# backplane.net
KiCad netlist of a schematic drawn in EAGLE
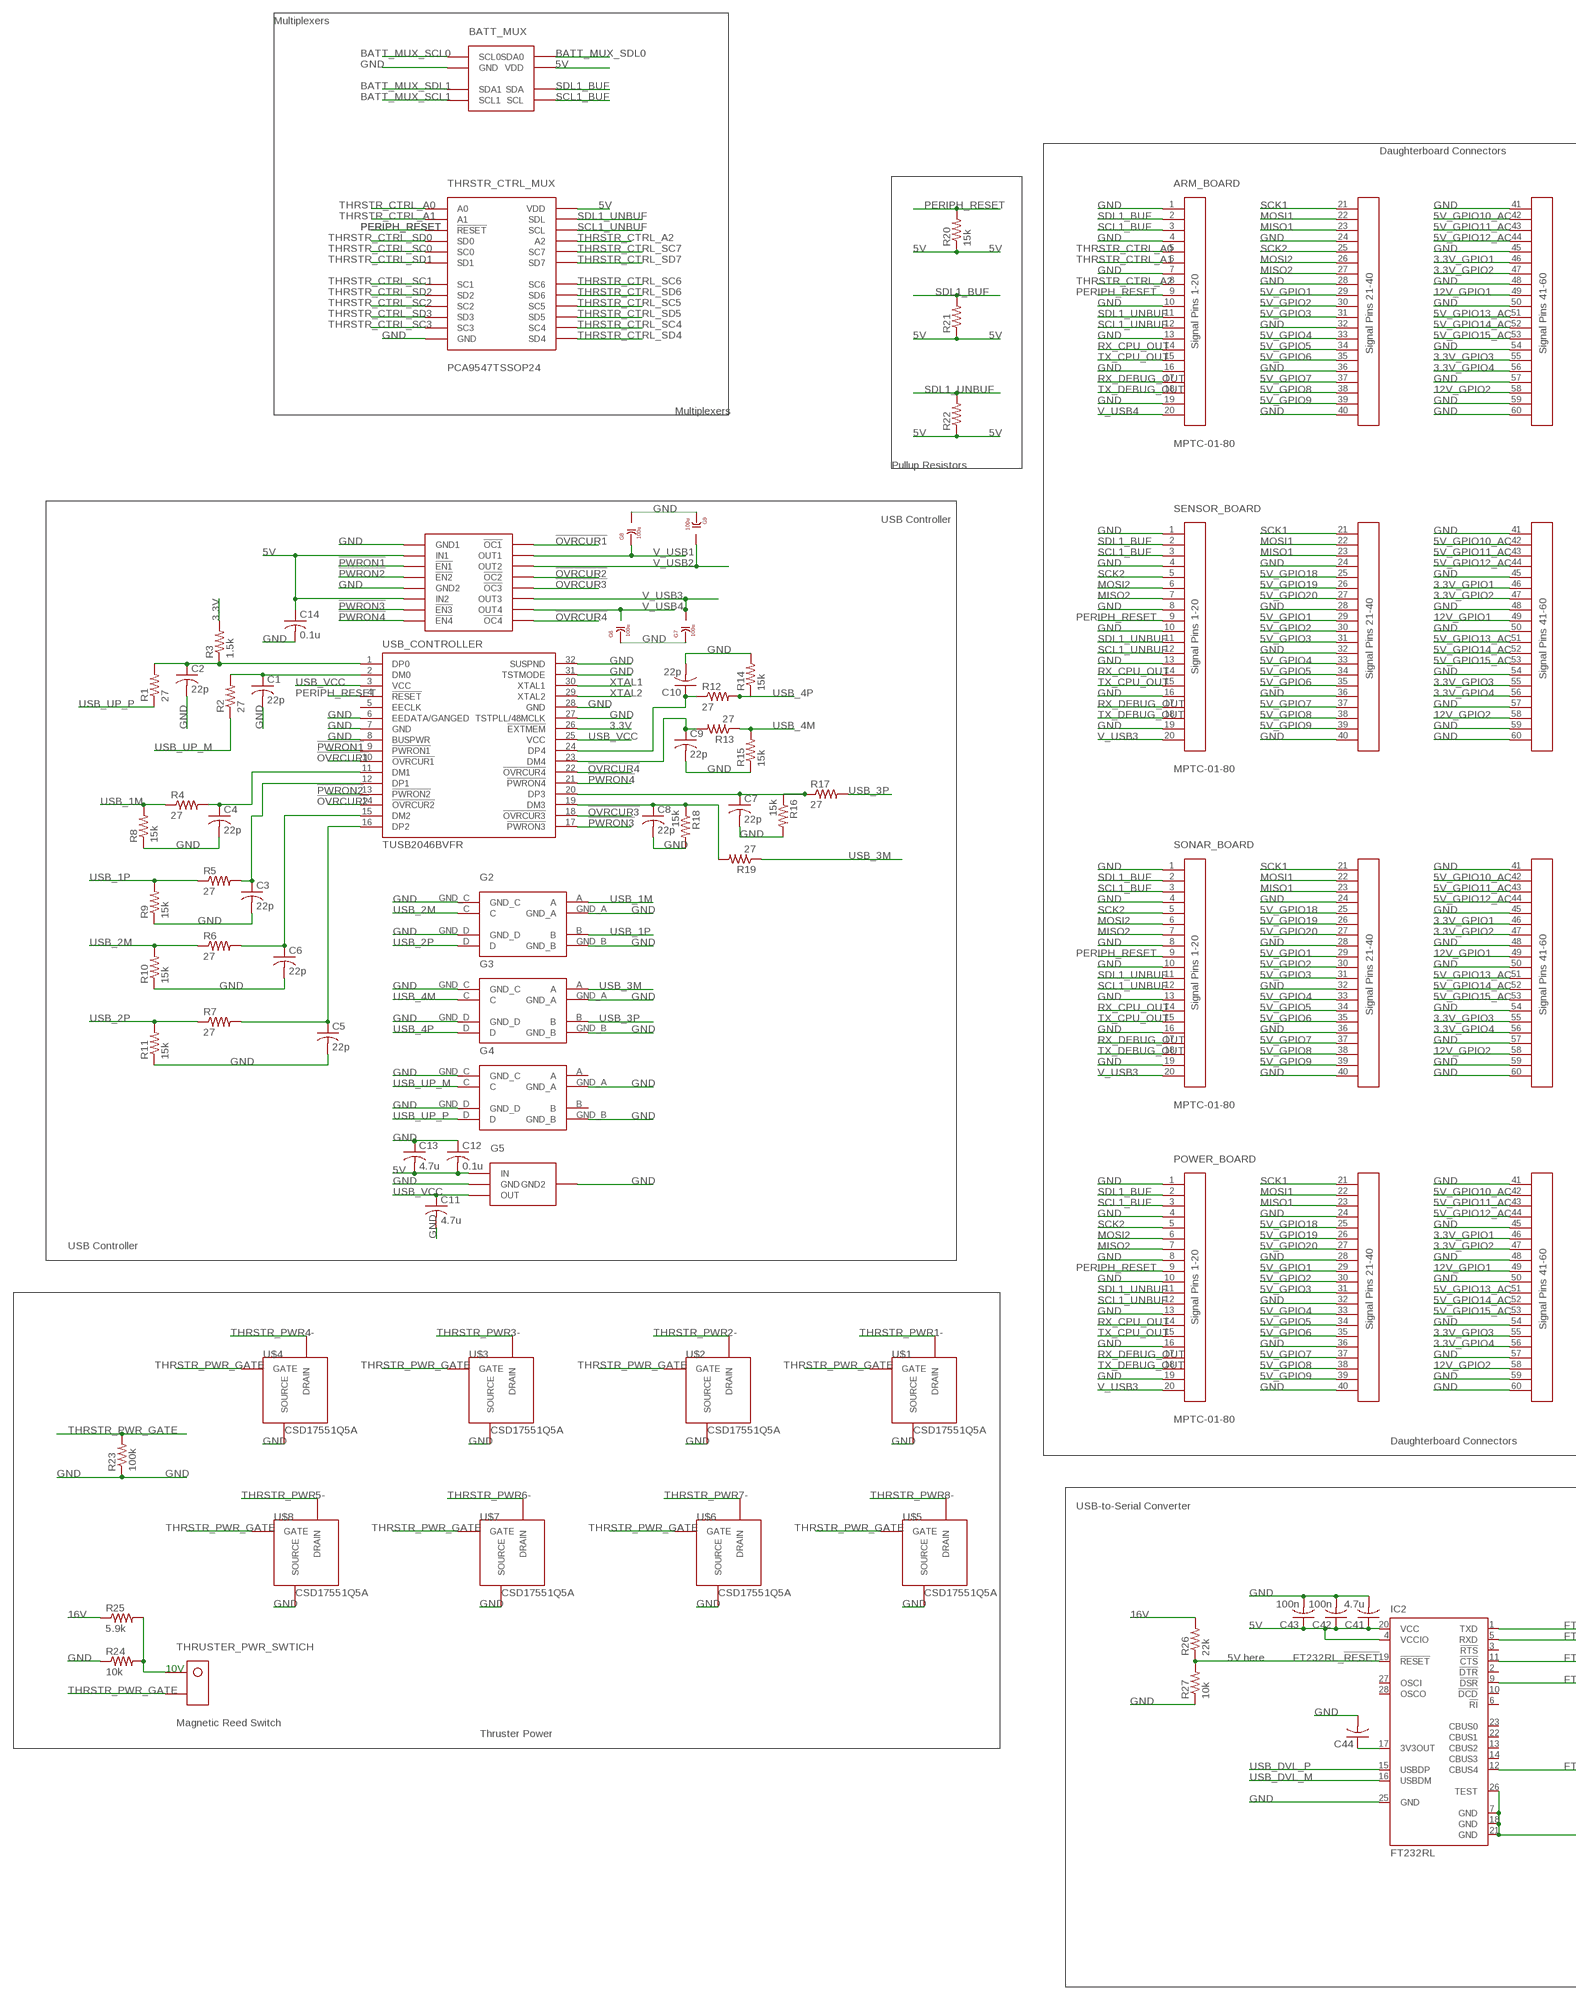
[diagram p0: schematic, sheet 1, part 1 of 2]
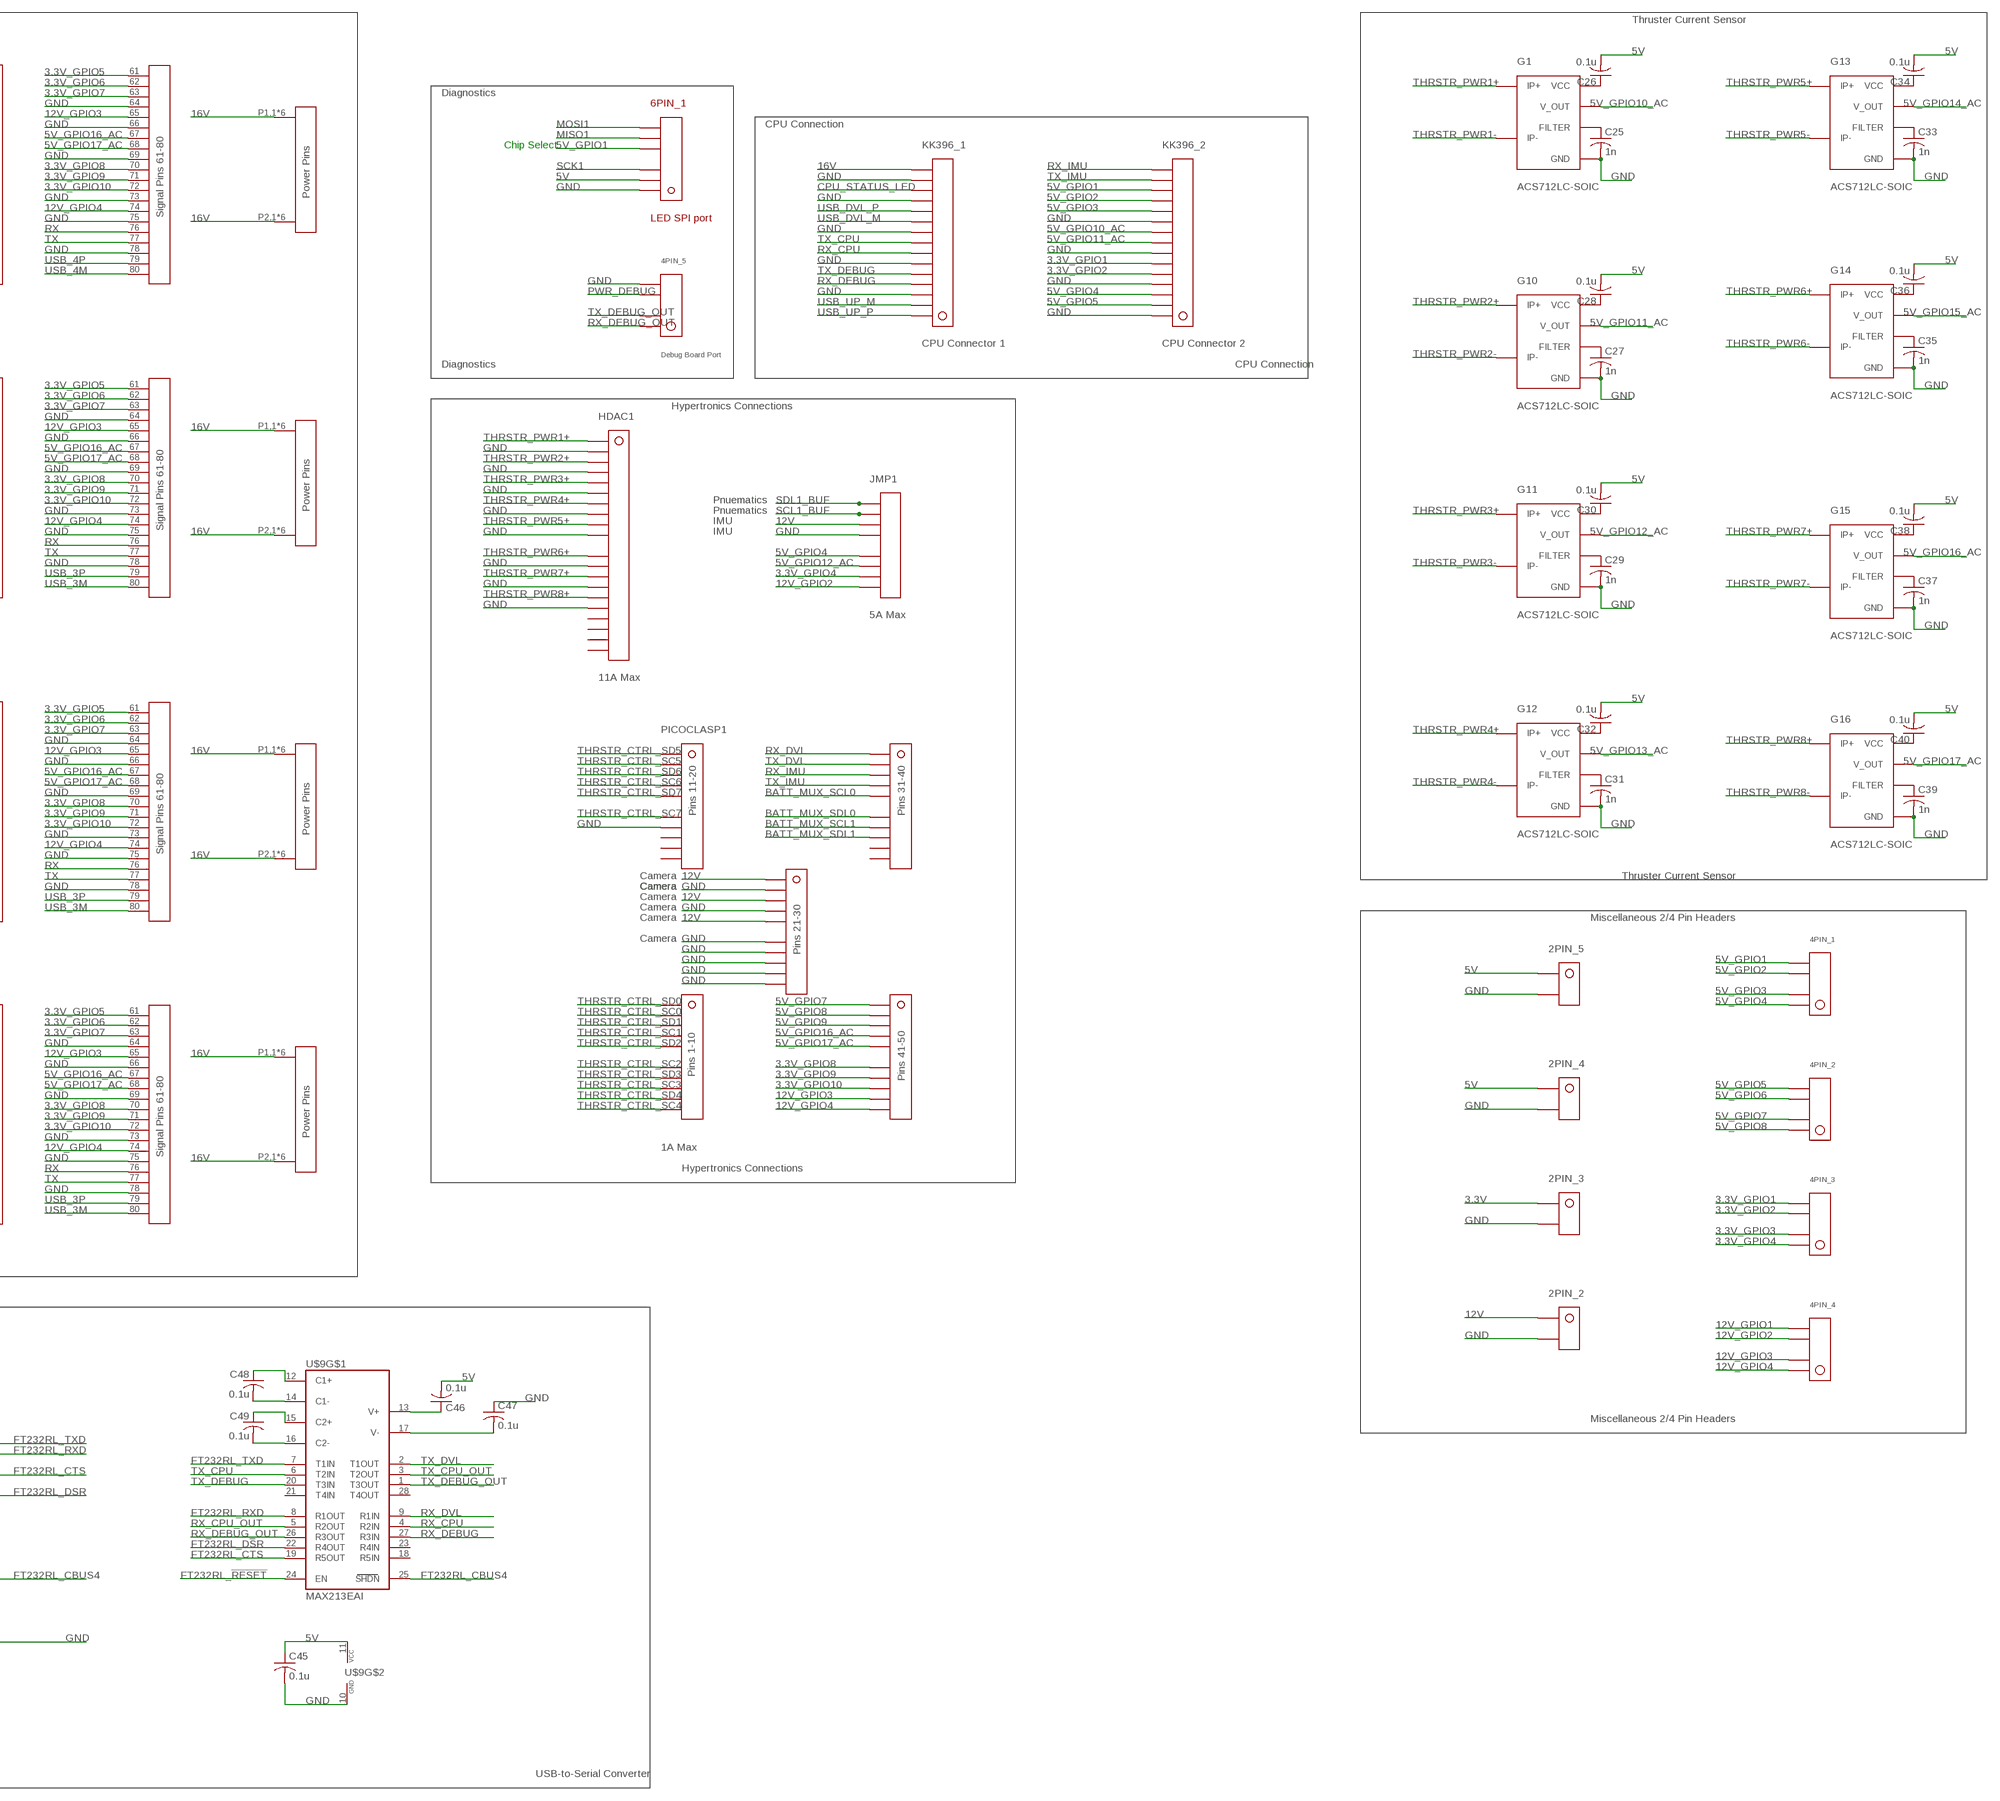
[diagram p1: schematic, sheet 1, part 2 of 2]

(export (version "E")
  (design (tool "Eeschema 10.0.6"))
  (components
    (comp (ref "2PIN_2")
      (value "KK254_VERT_2PIN22-29-2021")
      (footprint "eagle-import:KK254_VERT_2PIN")
      (libsource (lib "eagle-import") (part "KK254_VERT_2PIN22-29-2021"))
    )
    (comp (ref "2PIN_3")
      (value "KK254_VERT_2PIN22-29-2021")
      (footprint "eagle-import:KK254_VERT_2PIN")
      (libsource (lib "eagle-import") (part "KK254_VERT_2PIN22-29-2021"))
    )
    (comp (ref "2PIN_4")
      (value "KK254_VERT_2PIN22-29-2021")
      (footprint "eagle-import:KK254_VERT_2PIN")
      (libsource (lib "eagle-import") (part "KK254_VERT_2PIN22-29-2021"))
    )
    (comp (ref "2PIN_5")
      (value "KK254_VERT_2PIN22-29-2021")
      (footprint "eagle-import:KK254_VERT_2PIN")
      (libsource (lib "eagle-import") (part "KK254_VERT_2PIN22-29-2021"))
    )
    (comp (ref "4PIN_1")
      (value "KK254_VERT_4PIN22-29-2041")
      (footprint "eagle-import:KK254_VERT_4PIN")
      (libsource (lib "eagle-import") (part "KK254_VERT_4PIN22-29-2041"))
    )
    (comp (ref "4PIN_2")
      (value "KK254_VERT_4PIN22-29-2041")
      (footprint "eagle-import:KK254_VERT_4PIN")
      (libsource (lib "eagle-import") (part "KK254_VERT_4PIN22-29-2041"))
    )
    (comp (ref "4PIN_3")
      (value "KK254_VERT_4PIN22-29-2041")
      (footprint "eagle-import:KK254_VERT_4PIN")
      (libsource (lib "eagle-import") (part "KK254_VERT_4PIN22-29-2041"))
    )
    (comp (ref "4PIN_4")
      (value "KK254_VERT_4PIN22-29-2041")
      (footprint "eagle-import:KK254_VERT_4PIN")
      (libsource (lib "eagle-import") (part "KK254_VERT_4PIN22-29-2041"))
    )
    (comp (ref "4PIN_5")
      (value "Debug Board Port")
      (footprint "eagle-import:KK254_VERT_4PIN")
      (libsource (lib "eagle-import") (part "KK254_VERT_4PIN22-29-2041"))
    )
    (comp (ref "6PIN_1")
      (value "LED SPI port")
      (footprint "eagle-import:KK254_6PIN")
      (libsource (lib "eagle-import") (part "KK254_6PIN"))
    )
    (comp (ref "ARM_BOARD")
      (value "MPTC-01-80")
      (footprint "eagle-import:MPTC-01-80")
      (libsource (lib "eagle-import") (part "MPTC-01-80"))
    )
    (comp (ref "BATT_MUX")
      (value "PCA9540BTSSOP8")
      (footprint "eagle-import:PCA9540B")
      (libsource (lib "eagle-import") (part "PCA9540BTSSOP8"))
    )
    (comp (ref "C1")
      (value "22p")
      (footprint "eagle-import:C0603")
      (libsource (lib "eagle-import") (part "C-USC0603"))
    )
    (comp (ref "C2")
      (value "22p")
      (footprint "eagle-import:C0603")
      (libsource (lib "eagle-import") (part "C-USC0603"))
    )
    (comp (ref "C3")
      (value "22p")
      (footprint "eagle-import:C0603")
      (libsource (lib "eagle-import") (part "C-USC0603"))
    )
    (comp (ref "C4")
      (value "22p")
      (footprint "eagle-import:C0603")
      (libsource (lib "eagle-import") (part "C-USC0603"))
    )
    (comp (ref "C5")
      (value "22p")
      (footprint "eagle-import:C0603")
      (libsource (lib "eagle-import") (part "C-USC0603"))
    )
    (comp (ref "C6")
      (value "22p")
      (footprint "eagle-import:C0603")
      (libsource (lib "eagle-import") (part "C-USC0603"))
    )
    (comp (ref "C7")
      (value "22p")
      (footprint "eagle-import:C0603")
      (libsource (lib "eagle-import") (part "C-USC0603"))
    )
    (comp (ref "C8")
      (value "22p")
      (footprint "eagle-import:C0603")
      (libsource (lib "eagle-import") (part "C-USC0603"))
    )
    (comp (ref "C9")
      (value "22p")
      (footprint "eagle-import:C0603")
      (libsource (lib "eagle-import") (part "C-USC0603"))
    )
    (comp (ref "C10")
      (value "22p")
      (footprint "eagle-import:C0603")
      (libsource (lib "eagle-import") (part "C-USC0603"))
    )
    (comp (ref "C11")
      (value "4.7u")
      (footprint "eagle-import:C0603")
      (libsource (lib "eagle-import") (part "C-USC0603"))
    )
    (comp (ref "C12")
      (value "0.1u")
      (footprint "eagle-import:C0603")
      (libsource (lib "eagle-import") (part "C-USC0603"))
    )
    (comp (ref "C13")
      (value "4.7u")
      (footprint "eagle-import:C0603")
      (libsource (lib "eagle-import") (part "C-USC0603"))
    )
    (comp (ref "C14")
      (value "0.1u")
      (footprint "eagle-import:C0603")
      (libsource (lib "eagle-import") (part "C-USC0603"))
    )
    (comp (ref "C25")
      (value "1n")
      (footprint "eagle-import:C0603")
      (libsource (lib "eagle-import") (part "C-USC0603"))
    )
    (comp (ref "C26")
      (value "0.1u")
      (footprint "eagle-import:C0603")
      (libsource (lib "eagle-import") (part "C-USC0603"))
    )
    (comp (ref "C27")
      (value "1n")
      (footprint "eagle-import:C0603")
      (libsource (lib "eagle-import") (part "C-USC0603"))
    )
    (comp (ref "C28")
      (value "0.1u")
      (footprint "eagle-import:C0603")
      (libsource (lib "eagle-import") (part "C-USC0603"))
    )
    (comp (ref "C29")
      (value "1n")
      (footprint "eagle-import:C0603")
      (libsource (lib "eagle-import") (part "C-USC0603"))
    )
    (comp (ref "C30")
      (value "0.1u")
      (footprint "eagle-import:C0603")
      (libsource (lib "eagle-import") (part "C-USC0603"))
    )
    (comp (ref "C31")
      (value "1n")
      (footprint "eagle-import:C0603")
      (libsource (lib "eagle-import") (part "C-USC0603"))
    )
    (comp (ref "C32")
      (value "0.1u")
      (footprint "eagle-import:C0603")
      (libsource (lib "eagle-import") (part "C-USC0603"))
    )
    (comp (ref "C33")
      (value "1n")
      (footprint "eagle-import:C0603")
      (libsource (lib "eagle-import") (part "C-USC0603"))
    )
    (comp (ref "C34")
      (value "0.1u")
      (footprint "eagle-import:C0603")
      (libsource (lib "eagle-import") (part "C-USC0603"))
    )
    (comp (ref "C35")
      (value "1n")
      (footprint "eagle-import:C0603")
      (libsource (lib "eagle-import") (part "C-USC0603"))
    )
    (comp (ref "C36")
      (value "0.1u")
      (footprint "eagle-import:C0603")
      (libsource (lib "eagle-import") (part "C-USC0603"))
    )
    (comp (ref "C37")
      (value "1n")
      (footprint "eagle-import:C0603")
      (libsource (lib "eagle-import") (part "C-USC0603"))
    )
    (comp (ref "C38")
      (value "0.1u")
      (footprint "eagle-import:C0603")
      (libsource (lib "eagle-import") (part "C-USC0603"))
    )
    (comp (ref "C39")
      (value "1n")
      (footprint "eagle-import:C0603")
      (libsource (lib "eagle-import") (part "C-USC0603"))
    )
    (comp (ref "C40")
      (value "0.1u")
      (footprint "eagle-import:C0603")
      (libsource (lib "eagle-import") (part "C-USC0603"))
    )
    (comp (ref "C41")
      (value "4.7u")
      (footprint "eagle-import:C0603")
      (libsource (lib "eagle-import") (part "C-USC0603"))
    )
    (comp (ref "C42")
      (value "100n")
      (footprint "eagle-import:C0603")
      (libsource (lib "eagle-import") (part "C-USC0603"))
    )
    (comp (ref "C43")
      (value "100n")
      (footprint "eagle-import:C0603")
      (libsource (lib "eagle-import") (part "C-USC0603"))
    )
    (comp (ref "C44")
      (value "C-USC0603")
      (footprint "eagle-import:C0603")
      (libsource (lib "eagle-import") (part "C-USC0603"))
    )
    (comp (ref "C45")
      (value "0.1u")
      (footprint "eagle-import:C0603")
      (libsource (lib "eagle-import") (part "C-USC0603"))
    )
    (comp (ref "C46")
      (value "0.1u")
      (footprint "eagle-import:C0603")
      (libsource (lib "eagle-import") (part "C-USC0603"))
    )
    (comp (ref "C47")
      (value "0.1u")
      (footprint "eagle-import:C0603")
      (libsource (lib "eagle-import") (part "C-USC0603"))
    )
    (comp (ref "C48")
      (value "0.1u")
      (footprint "eagle-import:C0603")
      (libsource (lib "eagle-import") (part "C-USC0603"))
    )
    (comp (ref "C49")
      (value "0.1u")
      (footprint "eagle-import:C0603")
      (libsource (lib "eagle-import") (part "C-USC0603"))
    )
    (comp (ref "G1")
      (value "ACS712LC-SOIC")
      (footprint "eagle-import:ACS712-SOIC")
      (libsource (lib "eagle-import") (part "ACS712LC-SOIC"))
    )
    (comp (ref "G2")
      (value "SN75240PW'TSSOP")
      (footprint "eagle-import:SN75240PW")
      (libsource (lib "eagle-import") (part "SN75240PW'TSSOP"))
    )
    (comp (ref "G3")
      (value "SN75240PW'TSSOP")
      (footprint "eagle-import:SN75240PW")
      (libsource (lib "eagle-import") (part "SN75240PW'TSSOP"))
    )
    (comp (ref "G4")
      (value "SN75240PW'TSSOP")
      (footprint "eagle-import:SN75240PW")
      (libsource (lib "eagle-import") (part "SN75240PW'TSSOP"))
    )
    (comp (ref "G5")
      (value "LM3940IMP-3.3/NOPB")
      (footprint "eagle-import:SOT223-DCY")
      (libsource (lib "eagle-import") (part "LM3940IMP-3.3/NOPB"))
    )
    (comp (ref "G6")
      (value "100u")
      (footprint "eagle-import:F930J107MBA")
      (libsource (lib "eagle-import") (part "F930J107MBA"))
    )
    (comp (ref "G7")
      (value "100u")
      (footprint "eagle-import:F930J107MBA")
      (libsource (lib "eagle-import") (part "F930J107MBA"))
    )
    (comp (ref "G8")
      (value "100u")
      (footprint "eagle-import:F930J107MBA")
      (libsource (lib "eagle-import") (part "F930J107MBA"))
    )
    (comp (ref "G9")
      (value "100u")
      (footprint "eagle-import:F930J107MBA")
      (libsource (lib "eagle-import") (part "F930J107MBA"))
    )
    (comp (ref "G10")
      (value "ACS712LC-SOIC")
      (footprint "eagle-import:ACS712-SOIC")
      (libsource (lib "eagle-import") (part "ACS712LC-SOIC"))
    )
    (comp (ref "G11")
      (value "ACS712LC-SOIC")
      (footprint "eagle-import:ACS712-SOIC")
      (libsource (lib "eagle-import") (part "ACS712LC-SOIC"))
    )
    (comp (ref "G12")
      (value "ACS712LC-SOIC")
      (footprint "eagle-import:ACS712-SOIC")
      (libsource (lib "eagle-import") (part "ACS712LC-SOIC"))
    )
    (comp (ref "G13")
      (value "ACS712LC-SOIC")
      (footprint "eagle-import:ACS712-SOIC")
      (libsource (lib "eagle-import") (part "ACS712LC-SOIC"))
    )
    (comp (ref "G14")
      (value "ACS712LC-SOIC")
      (footprint "eagle-import:ACS712-SOIC")
      (libsource (lib "eagle-import") (part "ACS712LC-SOIC"))
    )
    (comp (ref "G15")
      (value "ACS712LC-SOIC")
      (footprint "eagle-import:ACS712-SOIC")
      (libsource (lib "eagle-import") (part "ACS712LC-SOIC"))
    )
    (comp (ref "G16")
      (value "ACS712LC-SOIC")
      (footprint "eagle-import:ACS712-SOIC")
      (libsource (lib "eagle-import") (part "ACS712LC-SOIC"))
    )
    (comp (ref "HDAC1")
      (value "11A Max")
      (footprint "eagle-import:HDAC64_VERT_20PIN")
      (libsource (lib "eagle-import") (part "HDAC64_VERT_20PIN30700-4122"))
    )
    (comp (ref "IC2")
      (value "FT232RL")
      (footprint "eagle-import:SSOP28")
      (libsource (lib "eagle-import") (part "FT232RL"))
    )
    (comp (ref "JMP1")
      (value "5A Max")
      (footprint "eagle-import:MICROFIT3_VERT_8PIN")
      (libsource (lib "eagle-import") (part "MICROFIT3_VERT_8PIN43045-0828"))
    )
    (comp (ref "KK396_1")
      (value "CPU Connector 1")
      (footprint "eagle-import:KK396_VERT_15PIN")
      (libsource (lib "eagle-import") (part "KK396_VERT_15PIN"))
    )
    (comp (ref "KK396_2")
      (value "CPU Connector 2")
      (footprint "eagle-import:KK396_VERT_15PIN")
      (libsource (lib "eagle-import") (part "KK396_VERT_15PIN"))
    )
    (comp (ref "PICOCLASP1")
      (value "1A Max")
      (footprint "eagle-import:PICOCLASP_VERT_50PIN")
      (libsource (lib "eagle-import") (part "PICOCLASP_VERT_50PINSMD"))
    )
    (comp (ref "POWER_BOARD")
      (value "MPTC-01-80")
      (footprint "eagle-import:MPTC-01-80")
      (libsource (lib "eagle-import") (part "MPTC-01-80"))
    )
    (comp (ref "R1")
      (value "27")
      (footprint "eagle-import:R0603")
      (libsource (lib "eagle-import") (part "R-US_R0603"))
    )
    (comp (ref "R2")
      (value "27")
      (footprint "eagle-import:R0603")
      (libsource (lib "eagle-import") (part "R-US_R0603"))
    )
    (comp (ref "R3")
      (value "1.5k")
      (footprint "eagle-import:R0603")
      (libsource (lib "eagle-import") (part "R-US_R0603"))
    )
    (comp (ref "R4")
      (value "27")
      (footprint "eagle-import:R0603")
      (libsource (lib "eagle-import") (part "R-US_R0603"))
    )
    (comp (ref "R5")
      (value "27")
      (footprint "eagle-import:R0603")
      (libsource (lib "eagle-import") (part "R-US_R0603"))
    )
    (comp (ref "R6")
      (value "27")
      (footprint "eagle-import:R0603")
      (libsource (lib "eagle-import") (part "R-US_R0603"))
    )
    (comp (ref "R7")
      (value "27")
      (footprint "eagle-import:R0603")
      (libsource (lib "eagle-import") (part "R-US_R0603"))
    )
    (comp (ref "R8")
      (value "15k")
      (footprint "eagle-import:R0603")
      (libsource (lib "eagle-import") (part "R-US_R0603"))
    )
    (comp (ref "R9")
      (value "15k")
      (footprint "eagle-import:R0603")
      (libsource (lib "eagle-import") (part "R-US_R0603"))
    )
    (comp (ref "R10")
      (value "15k")
      (footprint "eagle-import:R0603")
      (libsource (lib "eagle-import") (part "R-US_R0603"))
    )
    (comp (ref "R11")
      (value "15k")
      (footprint "eagle-import:R0603")
      (libsource (lib "eagle-import") (part "R-US_R0603"))
    )
    (comp (ref "R12")
      (value "27")
      (footprint "eagle-import:R0603")
      (libsource (lib "eagle-import") (part "R-US_R0603"))
    )
    (comp (ref "R13")
      (value "27")
      (footprint "eagle-import:R0603")
      (libsource (lib "eagle-import") (part "R-US_R0603"))
    )
    (comp (ref "R14")
      (value "15k")
      (footprint "eagle-import:R0603")
      (libsource (lib "eagle-import") (part "R-US_R0603"))
    )
    (comp (ref "R15")
      (value "15k")
      (footprint "eagle-import:R0603")
      (libsource (lib "eagle-import") (part "R-US_R0603"))
    )
    (comp (ref "R16")
      (value "15k")
      (footprint "eagle-import:R0603")
      (libsource (lib "eagle-import") (part "R-US_R0603"))
    )
    (comp (ref "R17")
      (value "27")
      (footprint "eagle-import:R0603")
      (libsource (lib "eagle-import") (part "R-US_R0603"))
    )
    (comp (ref "R18")
      (value "15k")
      (footprint "eagle-import:R0603")
      (libsource (lib "eagle-import") (part "R-US_R0603"))
    )
    (comp (ref "R19")
      (value "27")
      (footprint "eagle-import:R0603")
      (libsource (lib "eagle-import") (part "R-US_R0603"))
    )
    (comp (ref "R20")
      (value "15k")
      (footprint "eagle-import:R0603")
      (libsource (lib "eagle-import") (part "R-US_R0603"))
    )
    (comp (ref "R21")
      (value "R-US_R0603")
      (footprint "eagle-import:R0603")
      (libsource (lib "eagle-import") (part "R-US_R0603"))
    )
    (comp (ref "R22")
      (value "R-US_R0603")
      (footprint "eagle-import:R0603")
      (libsource (lib "eagle-import") (part "R-US_R0603"))
    )
    (comp (ref "R23")
      (value "100k")
      (footprint "eagle-import:R0603")
      (libsource (lib "eagle-import") (part "R-US_R0603"))
    )
    (comp (ref "R24")
      (value "10k")
      (footprint "eagle-import:R0603")
      (libsource (lib "eagle-import") (part "R-US_R0603"))
    )
    (comp (ref "R25")
      (value "5.9k")
      (footprint "eagle-import:R0603")
      (libsource (lib "eagle-import") (part "R-US_R0603"))
    )
    (comp (ref "R26")
      (value "22k")
      (footprint "eagle-import:R0603")
      (libsource (lib "eagle-import") (part "R-US_R0603"))
    )
    (comp (ref "R27")
      (value "10k")
      (footprint "eagle-import:R0603")
      (libsource (lib "eagle-import") (part "R-US_R0603"))
    )
    (comp (ref "SENSOR_BOARD")
      (value "MPTC-01-80")
      (footprint "eagle-import:MPTC-01-80")
      (libsource (lib "eagle-import") (part "MPTC-01-80"))
    )
    (comp (ref "SONAR_BOARD")
      (value "MPTC-01-80")
      (footprint "eagle-import:MPTC-01-80")
      (libsource (lib "eagle-import") (part "MPTC-01-80"))
    )
    (comp (ref "THRSTR_CTRL_MUX")
      (value "PCA9547TSSOP24")
      (footprint "eagle-import:PCA9547_TSSOP24")
      (libsource (lib "eagle-import") (part "PCA9547TSSOP24"))
    )
    (comp (ref "THRUSTER_PWR_SWTICH")
      (value "Magnetic Reed Switch")
      (footprint "eagle-import:KK254_VERT_2PIN")
      (libsource (lib "eagle-import") (part "KK254_VERT_2PIN22-29-2021"))
    )
    (comp (ref "U$1")
      (value "CSD17551Q5A")
      (footprint "eagle-import:CSD17551Q5A")
      (libsource (lib "eagle-import") (part "CSD17551Q5A"))
    )
    (comp (ref "U$2")
      (value "CSD17551Q5A")
      (footprint "eagle-import:CSD17551Q5A")
      (libsource (lib "eagle-import") (part "CSD17551Q5A"))
    )
    (comp (ref "U$3")
      (value "CSD17551Q5A")
      (footprint "eagle-import:CSD17551Q5A")
      (libsource (lib "eagle-import") (part "CSD17551Q5A"))
    )
    (comp (ref "U$4")
      (value "CSD17551Q5A")
      (footprint "eagle-import:CSD17551Q5A")
      (libsource (lib "eagle-import") (part "CSD17551Q5A"))
    )
    (comp (ref "U$5")
      (value "CSD17551Q5A")
      (footprint "eagle-import:CSD17551Q5A")
      (libsource (lib "eagle-import") (part "CSD17551Q5A"))
    )
    (comp (ref "U$6")
      (value "CSD17551Q5A")
      (footprint "eagle-import:CSD17551Q5A")
      (libsource (lib "eagle-import") (part "CSD17551Q5A"))
    )
    (comp (ref "U$7")
      (value "CSD17551Q5A")
      (footprint "eagle-import:CSD17551Q5A")
      (libsource (lib "eagle-import") (part "CSD17551Q5A"))
    )
    (comp (ref "U$8")
      (value "CSD17551Q5A")
      (footprint "eagle-import:CSD17551Q5A")
      (libsource (lib "eagle-import") (part "CSD17551Q5A"))
    )
    (comp (ref "U$9")
      (value "MAX213EAI")
      (footprint "eagle-import:SSOP28")
      (libsource (lib "eagle-import") (part "MAX213EAI"))
    )
    (comp (ref "USB_CONTROLLER")
      (value "TUSB2046BVFR")
      (footprint "eagle-import:VF_S-PQFP-G32")
      (fields (field (name "MF") "TEXAS INSTRUMENTS"))
      (libsource (lib "eagle-import") (part "TUSB2046BVFR"))
    )
    (comp (ref "USB_CURRENT")
      (value "TPS2044BBD-SOIC")
      (footprint "eagle-import:TPS2044")
      (libsource (lib "eagle-import") (part "TPS2044BBD-SOIC"))
    )
  )
  (nets
    (net (code "1") (name "/3.3V") (class "Default")
      (node (ref "2PIN_3") (pin "P$1") (pinfunction "P$1_P$1") (pintype "bidirectional"))
      (node (ref "R3") (pin "2") (pinfunction "2_2") (pintype "passive"))
      (node (ref "USB_CONTROLLER") (pin "26") (pinfunction "~{EXTMEM}_26") (pintype "input"))
    )
    (net (code "2") (name "/3.3V_GPIO1") (class "Default")
      (node (ref "4PIN_3") (pin "P$4") (pinfunction "P$4_P$4") (pintype "bidirectional"))
      (node (ref "ARM_BOARD") (pin "46") (pinfunction "P$46_46") (pintype "bidirectional"))
      (node (ref "KK396_2") (pin "P$6") (pinfunction "P$6_P$6") (pintype "bidirectional"))
      (node (ref "POWER_BOARD") (pin "46") (pinfunction "P$46_46") (pintype "bidirectional"))
      (node (ref "SENSOR_BOARD") (pin "46") (pinfunction "P$46_46") (pintype "bidirectional"))
      (node (ref "SONAR_BOARD") (pin "46") (pinfunction "P$46_46") (pintype "bidirectional"))
    )
    (net (code "3") (name "/3.3V_GPIO2") (class "Default")
      (node (ref "4PIN_3") (pin "P$3") (pinfunction "P$3_P$3") (pintype "bidirectional"))
      (node (ref "ARM_BOARD") (pin "47") (pinfunction "P$47_47") (pintype "bidirectional"))
      (node (ref "KK396_2") (pin "P$5") (pinfunction "P$5_P$5") (pintype "bidirectional"))
      (node (ref "POWER_BOARD") (pin "47") (pinfunction "P$47_47") (pintype "bidirectional"))
      (node (ref "SENSOR_BOARD") (pin "47") (pinfunction "P$47_47") (pintype "bidirectional"))
      (node (ref "SONAR_BOARD") (pin "47") (pinfunction "P$47_47") (pintype "bidirectional"))
    )
    (net (code "4") (name "/3.3V_GPIO3") (class "Default")
      (node (ref "4PIN_3") (pin "P$2") (pinfunction "P$2_P$2") (pintype "bidirectional"))
      (node (ref "ARM_BOARD") (pin "55") (pinfunction "P$55_55") (pintype "bidirectional"))
      (node (ref "POWER_BOARD") (pin "55") (pinfunction "P$55_55") (pintype "bidirectional"))
      (node (ref "SENSOR_BOARD") (pin "55") (pinfunction "P$55_55") (pintype "bidirectional"))
      (node (ref "SONAR_BOARD") (pin "55") (pinfunction "P$55_55") (pintype "bidirectional"))
    )
    (net (code "5") (name "/3.3V_GPIO4") (class "Default")
      (node (ref "4PIN_3") (pin "P$1") (pinfunction "P$1_P$1") (pintype "bidirectional"))
      (node (ref "ARM_BOARD") (pin "56") (pinfunction "P$56_56") (pintype "bidirectional"))
      (node (ref "JMP1") (pin "P$2") (pinfunction "P$2_P$2") (pintype "bidirectional"))
      (node (ref "POWER_BOARD") (pin "56") (pinfunction "P$56_56") (pintype "bidirectional"))
      (node (ref "SENSOR_BOARD") (pin "56") (pinfunction "P$56_56") (pintype "bidirectional"))
      (node (ref "SONAR_BOARD") (pin "56") (pinfunction "P$56_56") (pintype "bidirectional"))
    )
    (net (code "6") (name "/3.3V_GPIO5") (class "Default")
      (node (ref "ARM_BOARD") (pin "61") (pinfunction "P$61_61") (pintype "bidirectional"))
      (node (ref "POWER_BOARD") (pin "61") (pinfunction "P$61_61") (pintype "bidirectional"))
      (node (ref "SENSOR_BOARD") (pin "61") (pinfunction "P$61_61") (pintype "bidirectional"))
      (node (ref "SONAR_BOARD") (pin "61") (pinfunction "P$61_61") (pintype "bidirectional"))
    )
    (net (code "7") (name "/3.3V_GPIO6") (class "Default")
      (node (ref "ARM_BOARD") (pin "62") (pinfunction "P$62_62") (pintype "bidirectional"))
      (node (ref "POWER_BOARD") (pin "62") (pinfunction "P$62_62") (pintype "bidirectional"))
      (node (ref "SENSOR_BOARD") (pin "62") (pinfunction "P$62_62") (pintype "bidirectional"))
      (node (ref "SONAR_BOARD") (pin "62") (pinfunction "P$62_62") (pintype "bidirectional"))
    )
    (net (code "8") (name "/3.3V_GPIO7") (class "Default")
      (node (ref "ARM_BOARD") (pin "63") (pinfunction "P$63_63") (pintype "bidirectional"))
      (node (ref "POWER_BOARD") (pin "63") (pinfunction "P$63_63") (pintype "bidirectional"))
      (node (ref "SENSOR_BOARD") (pin "63") (pinfunction "P$63_63") (pintype "bidirectional"))
      (node (ref "SONAR_BOARD") (pin "63") (pinfunction "P$63_63") (pintype "bidirectional"))
    )
    (net (code "9") (name "/3.3V_GPIO8") (class "Default")
      (node (ref "ARM_BOARD") (pin "70") (pinfunction "P$70_70") (pintype "bidirectional"))
      (node (ref "PICOCLASP1") (pin "P$46") (pinfunction "P$46_P$46") (pintype "bidirectional"))
      (node (ref "POWER_BOARD") (pin "70") (pinfunction "P$70_70") (pintype "bidirectional"))
      (node (ref "SENSOR_BOARD") (pin "70") (pinfunction "P$70_70") (pintype "bidirectional"))
      (node (ref "SONAR_BOARD") (pin "70") (pinfunction "P$70_70") (pintype "bidirectional"))
    )
    (net (code "10") (name "/3.3V_GPIO9") (class "Default")
      (node (ref "ARM_BOARD") (pin "71") (pinfunction "P$71_71") (pintype "bidirectional"))
      (node (ref "PICOCLASP1") (pin "P$47") (pinfunction "P$47_P$47") (pintype "bidirectional"))
      (node (ref "POWER_BOARD") (pin "71") (pinfunction "P$71_71") (pintype "bidirectional"))
      (node (ref "SENSOR_BOARD") (pin "71") (pinfunction "P$71_71") (pintype "bidirectional"))
      (node (ref "SONAR_BOARD") (pin "71") (pinfunction "P$71_71") (pintype "bidirectional"))
    )
    (net (code "11") (name "/3.3V_GPIO10") (class "Default")
      (node (ref "ARM_BOARD") (pin "72") (pinfunction "P$72_72") (pintype "bidirectional"))
      (node (ref "PICOCLASP1") (pin "P$48") (pinfunction "P$48_P$48") (pintype "bidirectional"))
      (node (ref "POWER_BOARD") (pin "72") (pinfunction "P$72_72") (pintype "bidirectional"))
      (node (ref "SENSOR_BOARD") (pin "72") (pinfunction "P$72_72") (pintype "bidirectional"))
      (node (ref "SONAR_BOARD") (pin "72") (pinfunction "P$72_72") (pintype "bidirectional"))
    )
    (net (code "12") (name "/5V") (class "Default")
      (node (ref "2PIN_4") (pin "P$1") (pinfunction "P$1_P$1") (pintype "bidirectional"))
      (node (ref "2PIN_5") (pin "P$1") (pinfunction "P$1_P$1") (pintype "bidirectional"))
      (node (ref "6PIN_1") (pin "P$2") (pinfunction "P$2_P$2") (pintype "bidirectional"))
      (node (ref "BATT_MUX") (pin "VDD") (pinfunction "VDD_VDD") (pintype "bidirectional"))
      (node (ref "C12") (pin "2") (pinfunction "2_2") (pintype "passive"))
      (node (ref "C13") (pin "2") (pinfunction "2_2") (pintype "passive"))
      (node (ref "C14") (pin "1") (pinfunction "1_1") (pintype "passive"))
      (node (ref "C26") (pin "2") (pinfunction "2_2") (pintype "passive"))
      (node (ref "C28") (pin "2") (pinfunction "2_2") (pintype "passive"))
      (node (ref "C30") (pin "2") (pinfunction "2_2") (pintype "passive"))
      (node (ref "C32") (pin "2") (pinfunction "2_2") (pintype "passive"))
      (node (ref "C34") (pin "2") (pinfunction "2_2") (pintype "passive"))
      (node (ref "C36") (pin "2") (pinfunction "2_2") (pintype "passive"))
      (node (ref "C38") (pin "2") (pinfunction "2_2") (pintype "passive"))
      (node (ref "C40") (pin "2") (pinfunction "2_2") (pintype "passive"))
      (node (ref "C41") (pin "1") (pinfunction "1_1") (pintype "passive"))
      (node (ref "C42") (pin "1") (pinfunction "1_1") (pintype "passive"))
      (node (ref "C43") (pin "1") (pinfunction "1_1") (pintype "passive"))
      (node (ref "C45") (pin "1") (pinfunction "1_1") (pintype "passive"))
      (node (ref "C46") (pin "2") (pinfunction "2_2") (pintype "passive"))
      (node (ref "G5") (pin "1") (pinfunction "IN_1") (pintype "bidirectional"))
      (node (ref "IC2") (pin "20") (pinfunction "VCC_20") (pintype "power_in"))
      (node (ref "IC2") (pin "4") (pinfunction "VCCIO_4") (pintype "power_in"))
      (node (ref "R20") (pin "1") (pinfunction "1_1") (pintype "passive"))
      (node (ref "R21") (pin "1") (pinfunction "1_1") (pintype "passive"))
      (node (ref "R22") (pin "1") (pinfunction "1_1") (pintype "passive"))
      (node (ref "THRSTR_CTRL_MUX") (pin "24") (pinfunction "VDD_24") (pintype "power_in"))
      (node (ref "U$9") (pin "11") (pinfunction "VCC_11") (pintype "power_in"))
      (node (ref "USB_CURRENT") (pin "IN1") (pinfunction "IN1_IN1") (pintype "bidirectional"))
      (node (ref "USB_CURRENT") (pin "IN2") (pinfunction "IN2_IN2") (pintype "bidirectional"))
    )
    (net (code "13") (name "/5V_GPIO1") (class "Default")
      (node (ref "4PIN_1") (pin "P$4") (pinfunction "P$4_P$4") (pintype "bidirectional"))
      (node (ref "6PIN_1") (pin "P$4") (pinfunction "P$4_P$4") (pintype "bidirectional"))
      (node (ref "ARM_BOARD") (pin "29") (pinfunction "P$29_29") (pintype "bidirectional"))
      (node (ref "KK396_2") (pin "P$13") (pinfunction "P$13_P$13") (pintype "bidirectional"))
      (node (ref "POWER_BOARD") (pin "29") (pinfunction "P$29_29") (pintype "bidirectional"))
      (node (ref "SENSOR_BOARD") (pin "29") (pinfunction "P$29_29") (pintype "bidirectional"))
      (node (ref "SONAR_BOARD") (pin "29") (pinfunction "P$29_29") (pintype "bidirectional"))
    )
    (net (code "14") (name "/5V_GPIO2") (class "Default")
      (node (ref "4PIN_1") (pin "P$3") (pinfunction "P$3_P$3") (pintype "bidirectional"))
      (node (ref "ARM_BOARD") (pin "30") (pinfunction "P$30_30") (pintype "bidirectional"))
      (node (ref "KK396_2") (pin "P$12") (pinfunction "P$12_P$12") (pintype "bidirectional"))
      (node (ref "POWER_BOARD") (pin "30") (pinfunction "P$30_30") (pintype "bidirectional"))
      (node (ref "SENSOR_BOARD") (pin "30") (pinfunction "P$30_30") (pintype "bidirectional"))
      (node (ref "SONAR_BOARD") (pin "30") (pinfunction "P$30_30") (pintype "bidirectional"))
    )
    (net (code "15") (name "/5V_GPIO3") (class "Default")
      (node (ref "4PIN_1") (pin "P$2") (pinfunction "P$2_P$2") (pintype "bidirectional"))
      (node (ref "ARM_BOARD") (pin "31") (pinfunction "P$31_31") (pintype "bidirectional"))
      (node (ref "KK396_2") (pin "P$11") (pinfunction "P$11_P$11") (pintype "bidirectional"))
      (node (ref "POWER_BOARD") (pin "31") (pinfunction "P$31_31") (pintype "bidirectional"))
      (node (ref "SENSOR_BOARD") (pin "31") (pinfunction "P$31_31") (pintype "bidirectional"))
      (node (ref "SONAR_BOARD") (pin "31") (pinfunction "P$31_31") (pintype "bidirectional"))
    )
    (net (code "16") (name "/5V_GPIO4") (class "Default")
      (node (ref "4PIN_1") (pin "P$1") (pinfunction "P$1_P$1") (pintype "bidirectional"))
      (node (ref "ARM_BOARD") (pin "33") (pinfunction "P$33_33") (pintype "bidirectional"))
      (node (ref "JMP1") (pin "P$4") (pinfunction "P$4_P$4") (pintype "bidirectional"))
      (node (ref "KK396_2") (pin "P$3") (pinfunction "P$3_P$3") (pintype "bidirectional"))
      (node (ref "POWER_BOARD") (pin "33") (pinfunction "P$33_33") (pintype "bidirectional"))
      (node (ref "SENSOR_BOARD") (pin "33") (pinfunction "P$33_33") (pintype "bidirectional"))
      (node (ref "SONAR_BOARD") (pin "33") (pinfunction "P$33_33") (pintype "bidirectional"))
    )
    (net (code "17") (name "/5V_GPIO5") (class "Default")
      (node (ref "4PIN_2") (pin "P$4") (pinfunction "P$4_P$4") (pintype "bidirectional"))
      (node (ref "ARM_BOARD") (pin "34") (pinfunction "P$34_34") (pintype "bidirectional"))
      (node (ref "KK396_2") (pin "P$2") (pinfunction "P$2_P$2") (pintype "bidirectional"))
      (node (ref "POWER_BOARD") (pin "34") (pinfunction "P$34_34") (pintype "bidirectional"))
      (node (ref "SENSOR_BOARD") (pin "34") (pinfunction "P$34_34") (pintype "bidirectional"))
      (node (ref "SONAR_BOARD") (pin "34") (pinfunction "P$34_34") (pintype "bidirectional"))
    )
    (net (code "18") (name "/5V_GPIO6") (class "Default")
      (node (ref "4PIN_2") (pin "P$3") (pinfunction "P$3_P$3") (pintype "bidirectional"))
      (node (ref "ARM_BOARD") (pin "35") (pinfunction "P$35_35") (pintype "bidirectional"))
      (node (ref "POWER_BOARD") (pin "35") (pinfunction "P$35_35") (pintype "bidirectional"))
      (node (ref "SENSOR_BOARD") (pin "35") (pinfunction "P$35_35") (pintype "bidirectional"))
      (node (ref "SONAR_BOARD") (pin "35") (pinfunction "P$35_35") (pintype "bidirectional"))
    )
    (net (code "19") (name "/5V_GPIO7") (class "Default")
      (node (ref "4PIN_2") (pin "P$2") (pinfunction "P$2_P$2") (pintype "bidirectional"))
      (node (ref "ARM_BOARD") (pin "37") (pinfunction "P$37_37") (pintype "bidirectional"))
      (node (ref "PICOCLASP1") (pin "P$41") (pinfunction "P$41_P$41") (pintype "bidirectional"))
      (node (ref "POWER_BOARD") (pin "37") (pinfunction "P$37_37") (pintype "bidirectional"))
      (node (ref "SENSOR_BOARD") (pin "37") (pinfunction "P$37_37") (pintype "bidirectional"))
      (node (ref "SONAR_BOARD") (pin "37") (pinfunction "P$37_37") (pintype "bidirectional"))
    )
    (net (code "20") (name "/5V_GPIO8") (class "Default")
      (node (ref "4PIN_2") (pin "P$1") (pinfunction "P$1_P$1") (pintype "bidirectional"))
      (node (ref "ARM_BOARD") (pin "38") (pinfunction "P$38_38") (pintype "bidirectional"))
      (node (ref "PICOCLASP1") (pin "P$42") (pinfunction "P$42_P$42") (pintype "bidirectional"))
      (node (ref "POWER_BOARD") (pin "38") (pinfunction "P$38_38") (pintype "bidirectional"))
      (node (ref "SENSOR_BOARD") (pin "38") (pinfunction "P$38_38") (pintype "bidirectional"))
      (node (ref "SONAR_BOARD") (pin "38") (pinfunction "P$38_38") (pintype "bidirectional"))
    )
    (net (code "21") (name "/5V_GPIO9") (class "Default")
      (node (ref "ARM_BOARD") (pin "39") (pinfunction "P$39_39") (pintype "bidirectional"))
      (node (ref "PICOCLASP1") (pin "P$43") (pinfunction "P$43_P$43") (pintype "bidirectional"))
      (node (ref "POWER_BOARD") (pin "39") (pinfunction "P$39_39") (pintype "bidirectional"))
      (node (ref "SENSOR_BOARD") (pin "39") (pinfunction "P$39_39") (pintype "bidirectional"))
      (node (ref "SONAR_BOARD") (pin "39") (pinfunction "P$39_39") (pintype "bidirectional"))
    )
    (net (code "22") (name "/5V_GPIO10_AC") (class "Default")
      (node (ref "ARM_BOARD") (pin "42") (pinfunction "P$42_42") (pintype "bidirectional"))
      (node (ref "G1") (pin "V_OUT") (pinfunction "V_OUT_V_OUT") (pintype "bidirectional"))
      (node (ref "KK396_2") (pin "P$9") (pinfunction "P$9_P$9") (pintype "bidirectional"))
      (node (ref "POWER_BOARD") (pin "42") (pinfunction "P$42_42") (pintype "bidirectional"))
      (node (ref "SENSOR_BOARD") (pin "42") (pinfunction "P$42_42") (pintype "bidirectional"))
      (node (ref "SONAR_BOARD") (pin "42") (pinfunction "P$42_42") (pintype "bidirectional"))
    )
    (net (code "23") (name "/5V_GPIO11_AC") (class "Default")
      (node (ref "ARM_BOARD") (pin "43") (pinfunction "P$43_43") (pintype "bidirectional"))
      (node (ref "G10") (pin "V_OUT") (pinfunction "V_OUT_V_OUT") (pintype "bidirectional"))
      (node (ref "KK396_2") (pin "P$8") (pinfunction "P$8_P$8") (pintype "bidirectional"))
      (node (ref "POWER_BOARD") (pin "43") (pinfunction "P$43_43") (pintype "bidirectional"))
      (node (ref "SENSOR_BOARD") (pin "43") (pinfunction "P$43_43") (pintype "bidirectional"))
      (node (ref "SONAR_BOARD") (pin "43") (pinfunction "P$43_43") (pintype "bidirectional"))
    )
    (net (code "24") (name "/5V_GPIO12_AC") (class "Default")
      (node (ref "ARM_BOARD") (pin "44") (pinfunction "P$44_44") (pintype "bidirectional"))
      (node (ref "G11") (pin "V_OUT") (pinfunction "V_OUT_V_OUT") (pintype "bidirectional"))
      (node (ref "JMP1") (pin "P$3") (pinfunction "P$3_P$3") (pintype "bidirectional"))
      (node (ref "POWER_BOARD") (pin "44") (pinfunction "P$44_44") (pintype "bidirectional"))
      (node (ref "SENSOR_BOARD") (pin "44") (pinfunction "P$44_44") (pintype "bidirectional"))
      (node (ref "SONAR_BOARD") (pin "44") (pinfunction "P$44_44") (pintype "bidirectional"))
    )
    (net (code "25") (name "/5V_GPIO13_AC") (class "Default")
      (node (ref "ARM_BOARD") (pin "51") (pinfunction "P$51_51") (pintype "bidirectional"))
      (node (ref "G12") (pin "V_OUT") (pinfunction "V_OUT_V_OUT") (pintype "bidirectional"))
      (node (ref "POWER_BOARD") (pin "51") (pinfunction "P$51_51") (pintype "bidirectional"))
      (node (ref "SENSOR_BOARD") (pin "51") (pinfunction "P$51_51") (pintype "bidirectional"))
      (node (ref "SONAR_BOARD") (pin "51") (pinfunction "P$51_51") (pintype "bidirectional"))
    )
    (net (code "26") (name "/5V_GPIO14_AC") (class "Default")
      (node (ref "ARM_BOARD") (pin "52") (pinfunction "P$52_52") (pintype "bidirectional"))
      (node (ref "G13") (pin "V_OUT") (pinfunction "V_OUT_V_OUT") (pintype "bidirectional"))
      (node (ref "POWER_BOARD") (pin "52") (pinfunction "P$52_52") (pintype "bidirectional"))
      (node (ref "SENSOR_BOARD") (pin "52") (pinfunction "P$52_52") (pintype "bidirectional"))
      (node (ref "SONAR_BOARD") (pin "52") (pinfunction "P$52_52") (pintype "bidirectional"))
    )
    (net (code "27") (name "/5V_GPIO15_AC") (class "Default")
      (node (ref "ARM_BOARD") (pin "53") (pinfunction "P$53_53") (pintype "bidirectional"))
      (node (ref "G14") (pin "V_OUT") (pinfunction "V_OUT_V_OUT") (pintype "bidirectional"))
      (node (ref "POWER_BOARD") (pin "53") (pinfunction "P$53_53") (pintype "bidirectional"))
      (node (ref "SENSOR_BOARD") (pin "53") (pinfunction "P$53_53") (pintype "bidirectional"))
      (node (ref "SONAR_BOARD") (pin "53") (pinfunction "P$53_53") (pintype "bidirectional"))
    )
    (net (code "28") (name "/5V_GPIO16_AC") (class "Default")
      (node (ref "ARM_BOARD") (pin "67") (pinfunction "P$67_67") (pintype "bidirectional"))
      (node (ref "G15") (pin "V_OUT") (pinfunction "V_OUT_V_OUT") (pintype "bidirectional"))
      (node (ref "PICOCLASP1") (pin "P$44") (pinfunction "P$44_P$44") (pintype "bidirectional"))
      (node (ref "POWER_BOARD") (pin "67") (pinfunction "P$67_67") (pintype "bidirectional"))
      (node (ref "SENSOR_BOARD") (pin "67") (pinfunction "P$67_67") (pintype "bidirectional"))
      (node (ref "SONAR_BOARD") (pin "67") (pinfunction "P$67_67") (pintype "bidirectional"))
    )
    (net (code "29") (name "/5V_GPIO17_AC") (class "Default")
      (node (ref "ARM_BOARD") (pin "68") (pinfunction "P$68_68") (pintype "bidirectional"))
      (node (ref "G16") (pin "V_OUT") (pinfunction "V_OUT_V_OUT") (pintype "bidirectional"))
      (node (ref "PICOCLASP1") (pin "P$45") (pinfunction "P$45_P$45") (pintype "bidirectional"))
      (node (ref "POWER_BOARD") (pin "68") (pinfunction "P$68_68") (pintype "bidirectional"))
      (node (ref "SENSOR_BOARD") (pin "68") (pinfunction "P$68_68") (pintype "bidirectional"))
      (node (ref "SONAR_BOARD") (pin "68") (pinfunction "P$68_68") (pintype "bidirectional"))
    )
    (net (code "30") (name "/5V_GPIO18") (class "Default")
      (node (ref "POWER_BOARD") (pin "25") (pinfunction "P$25_25") (pintype "bidirectional"))
      (node (ref "SENSOR_BOARD") (pin "25") (pinfunction "P$25_25") (pintype "bidirectional"))
      (node (ref "SONAR_BOARD") (pin "25") (pinfunction "P$25_25") (pintype "bidirectional"))
    )
    (net (code "31") (name "/5V_GPIO19") (class "Default")
      (node (ref "POWER_BOARD") (pin "26") (pinfunction "P$26_26") (pintype "bidirectional"))
      (node (ref "SENSOR_BOARD") (pin "26") (pinfunction "P$26_26") (pintype "bidirectional"))
      (node (ref "SONAR_BOARD") (pin "26") (pinfunction "P$26_26") (pintype "bidirectional"))
    )
    (net (code "32") (name "/5V_GPIO20") (class "Default")
      (node (ref "POWER_BOARD") (pin "27") (pinfunction "P$27_27") (pintype "bidirectional"))
      (node (ref "SENSOR_BOARD") (pin "27") (pinfunction "P$27_27") (pintype "bidirectional"))
      (node (ref "SONAR_BOARD") (pin "27") (pinfunction "P$27_27") (pintype "bidirectional"))
    )
    (net (code "33") (name "/12V") (class "Default")
      (node (ref "2PIN_2") (pin "P$1") (pinfunction "P$1_P$1") (pintype "bidirectional"))
      (node (ref "JMP1") (pin "P$6") (pinfunction "P$6_P$6") (pintype "bidirectional"))
      (node (ref "PICOCLASP1") (pin "P$21") (pinfunction "P$21_P$21") (pintype "bidirectional"))
      (node (ref "PICOCLASP1") (pin "P$23") (pinfunction "P$23_P$23") (pintype "bidirectional"))
      (node (ref "PICOCLASP1") (pin "P$25") (pinfunction "P$25_P$25") (pintype "bidirectional"))
    )
    (net (code "34") (name "/12V_GPIO1") (class "Default")
      (node (ref "4PIN_4") (pin "P$4") (pinfunction "P$4_P$4") (pintype "bidirectional"))
      (node (ref "ARM_BOARD") (pin "49") (pinfunction "P$49_49") (pintype "bidirectional"))
      (node (ref "POWER_BOARD") (pin "49") (pinfunction "P$49_49") (pintype "bidirectional"))
      (node (ref "SENSOR_BOARD") (pin "49") (pinfunction "P$49_49") (pintype "bidirectional"))
      (node (ref "SONAR_BOARD") (pin "49") (pinfunction "P$49_49") (pintype "bidirectional"))
    )
    (net (code "35") (name "/12V_GPIO2") (class "Default")
      (node (ref "4PIN_4") (pin "P$3") (pinfunction "P$3_P$3") (pintype "bidirectional"))
      (node (ref "ARM_BOARD") (pin "58") (pinfunction "P$58_58") (pintype "bidirectional"))
      (node (ref "JMP1") (pin "P$1") (pinfunction "P$1_P$1") (pintype "bidirectional"))
      (node (ref "POWER_BOARD") (pin "58") (pinfunction "P$58_58") (pintype "bidirectional"))
      (node (ref "SENSOR_BOARD") (pin "58") (pinfunction "P$58_58") (pintype "bidirectional"))
      (node (ref "SONAR_BOARD") (pin "58") (pinfunction "P$58_58") (pintype "bidirectional"))
    )
    (net (code "36") (name "/12V_GPIO3") (class "Default")
      (node (ref "4PIN_4") (pin "P$2") (pinfunction "P$2_P$2") (pintype "bidirectional"))
      (node (ref "ARM_BOARD") (pin "65") (pinfunction "P$65_65") (pintype "bidirectional"))
      (node (ref "PICOCLASP1") (pin "P$49") (pinfunction "P$49_P$49") (pintype "bidirectional"))
      (node (ref "POWER_BOARD") (pin "65") (pinfunction "P$65_65") (pintype "bidirectional"))
      (node (ref "SENSOR_BOARD") (pin "65") (pinfunction "P$65_65") (pintype "bidirectional"))
      (node (ref "SONAR_BOARD") (pin "65") (pinfunction "P$65_65") (pintype "bidirectional"))
    )
    (net (code "37") (name "/12V_GPIO4") (class "Default")
      (node (ref "4PIN_4") (pin "P$1") (pinfunction "P$1_P$1") (pintype "bidirectional"))
      (node (ref "ARM_BOARD") (pin "74") (pinfunction "P$74_74") (pintype "bidirectional"))
      (node (ref "PICOCLASP1") (pin "P$50") (pinfunction "P$50_P$50") (pintype "bidirectional"))
      (node (ref "POWER_BOARD") (pin "74") (pinfunction "P$74_74") (pintype "bidirectional"))
      (node (ref "SENSOR_BOARD") (pin "74") (pinfunction "P$74_74") (pintype "bidirectional"))
      (node (ref "SONAR_BOARD") (pin "74") (pinfunction "P$74_74") (pintype "bidirectional"))
    )
    (net (code "38") (name "/16V") (class "Default")
      (node (ref "ARM_BOARD") (pin "P1,1") (pinfunction "POWER1_P1,1") (pintype "bidirectional"))
      (node (ref "ARM_BOARD") (pin "P1,2") (pinfunction "POWER1_P1,2") (pintype "bidirectional"))
      (node (ref "ARM_BOARD") (pin "P1,3") (pinfunction "POWER1_P1,3") (pintype "bidirectional"))
      (node (ref "ARM_BOARD") (pin "P1,4") (pinfunction "POWER1_P1,4") (pintype "bidirectional"))
      (node (ref "ARM_BOARD") (pin "P1,5") (pinfunction "POWER1_P1,5") (pintype "bidirectional"))
      (node (ref "ARM_BOARD") (pin "P1,6") (pinfunction "POWER1_P1,6") (pintype "bidirectional"))
      (node (ref "ARM_BOARD") (pin "P2,1") (pinfunction "POWER2_P2,1") (pintype "bidirectional"))
      (node (ref "ARM_BOARD") (pin "P2,2") (pinfunction "POWER2_P2,2") (pintype "bidirectional"))
      (node (ref "ARM_BOARD") (pin "P2,3") (pinfunction "POWER2_P2,3") (pintype "bidirectional"))
      (node (ref "ARM_BOARD") (pin "P2,4") (pinfunction "POWER2_P2,4") (pintype "bidirectional"))
      (node (ref "ARM_BOARD") (pin "P2,5") (pinfunction "POWER2_P2,5") (pintype "bidirectional"))
      (node (ref "ARM_BOARD") (pin "P2,6") (pinfunction "POWER2_P2,6") (pintype "bidirectional"))
      (node (ref "KK396_1") (pin "P$15") (pinfunction "P$15_P$15") (pintype "bidirectional"))
      (node (ref "POWER_BOARD") (pin "P1,1") (pinfunction "POWER1_P1,1") (pintype "bidirectional"))
      (node (ref "POWER_BOARD") (pin "P1,2") (pinfunction "POWER1_P1,2") (pintype "bidirectional"))
      (node (ref "POWER_BOARD") (pin "P1,3") (pinfunction "POWER1_P1,3") (pintype "bidirectional"))
      (node (ref "POWER_BOARD") (pin "P1,4") (pinfunction "POWER1_P1,4") (pintype "bidirectional"))
      (node (ref "POWER_BOARD") (pin "P1,5") (pinfunction "POWER1_P1,5") (pintype "bidirectional"))
      (node (ref "POWER_BOARD") (pin "P1,6") (pinfunction "POWER1_P1,6") (pintype "bidirectional"))
      (node (ref "POWER_BOARD") (pin "P2,1") (pinfunction "POWER2_P2,1") (pintype "bidirectional"))
      (node (ref "POWER_BOARD") (pin "P2,2") (pinfunction "POWER2_P2,2") (pintype "bidirectional"))
      (node (ref "POWER_BOARD") (pin "P2,3") (pinfunction "POWER2_P2,3") (pintype "bidirectional"))
      (node (ref "POWER_BOARD") (pin "P2,4") (pinfunction "POWER2_P2,4") (pintype "bidirectional"))
      (node (ref "POWER_BOARD") (pin "P2,5") (pinfunction "POWER2_P2,5") (pintype "bidirectional"))
      (node (ref "POWER_BOARD") (pin "P2,6") (pinfunction "POWER2_P2,6") (pintype "bidirectional"))
      (node (ref "R25") (pin "1") (pinfunction "1_1") (pintype "passive"))
      (node (ref "R26") (pin "2") (pinfunction "2_2") (pintype "passive"))
      (node (ref "SENSOR_BOARD") (pin "P1,1") (pinfunction "POWER1_P1,1") (pintype "bidirectional"))
      (node (ref "SENSOR_BOARD") (pin "P1,2") (pinfunction "POWER1_P1,2") (pintype "bidirectional"))
      (node (ref "SENSOR_BOARD") (pin "P1,3") (pinfunction "POWER1_P1,3") (pintype "bidirectional"))
      (node (ref "SENSOR_BOARD") (pin "P1,4") (pinfunction "POWER1_P1,4") (pintype "bidirectional"))
      (node (ref "SENSOR_BOARD") (pin "P1,5") (pinfunction "POWER1_P1,5") (pintype "bidirectional"))
      (node (ref "SENSOR_BOARD") (pin "P1,6") (pinfunction "POWER1_P1,6") (pintype "bidirectional"))
      (node (ref "SENSOR_BOARD") (pin "P2,1") (pinfunction "POWER2_P2,1") (pintype "bidirectional"))
      (node (ref "SENSOR_BOARD") (pin "P2,2") (pinfunction "POWER2_P2,2") (pintype "bidirectional"))
      (node (ref "SENSOR_BOARD") (pin "P2,3") (pinfunction "POWER2_P2,3") (pintype "bidirectional"))
      (node (ref "SENSOR_BOARD") (pin "P2,4") (pinfunction "POWER2_P2,4") (pintype "bidirectional"))
      (node (ref "SENSOR_BOARD") (pin "P2,5") (pinfunction "POWER2_P2,5") (pintype "bidirectional"))
      (node (ref "SENSOR_BOARD") (pin "P2,6") (pinfunction "POWER2_P2,6") (pintype "bidirectional"))
      (node (ref "SONAR_BOARD") (pin "P1,1") (pinfunction "POWER1_P1,1") (pintype "bidirectional"))
      (node (ref "SONAR_BOARD") (pin "P1,2") (pinfunction "POWER1_P1,2") (pintype "bidirectional"))
      (node (ref "SONAR_BOARD") (pin "P1,3") (pinfunction "POWER1_P1,3") (pintype "bidirectional"))
      (node (ref "SONAR_BOARD") (pin "P1,4") (pinfunction "POWER1_P1,4") (pintype "bidirectional"))
      (node (ref "SONAR_BOARD") (pin "P1,5") (pinfunction "POWER1_P1,5") (pintype "bidirectional"))
      (node (ref "SONAR_BOARD") (pin "P1,6") (pinfunction "POWER1_P1,6") (pintype "bidirectional"))
      (node (ref "SONAR_BOARD") (pin "P2,1") (pinfunction "POWER2_P2,1") (pintype "bidirectional"))
      (node (ref "SONAR_BOARD") (pin "P2,2") (pinfunction "POWER2_P2,2") (pintype "bidirectional"))
      (node (ref "SONAR_BOARD") (pin "P2,3") (pinfunction "POWER2_P2,3") (pintype "bidirectional"))
      (node (ref "SONAR_BOARD") (pin "P2,4") (pinfunction "POWER2_P2,4") (pintype "bidirectional"))
      (node (ref "SONAR_BOARD") (pin "P2,5") (pinfunction "POWER2_P2,5") (pintype "bidirectional"))
      (node (ref "SONAR_BOARD") (pin "P2,6") (pinfunction "POWER2_P2,6") (pintype "bidirectional"))
    )
    (net (code "39") (name "/BATT_MUX_SCL0") (class "Default")
      (node (ref "BATT_MUX") (pin "SCL0") (pinfunction "SCL0_SCL0") (pintype "bidirectional"))
      (node (ref "PICOCLASP1") (pin "P$35") (pinfunction "P$35_P$35") (pintype "bidirectional"))
    )
    (net (code "40") (name "/BATT_MUX_SCL1") (class "Default")
      (node (ref "BATT_MUX") (pin "SCL1") (pinfunction "SCL1_SCL1") (pintype "bidirectional"))
      (node (ref "PICOCLASP1") (pin "P$37") (pinfunction "P$37_P$37") (pintype "bidirectional"))
    )
    (net (code "41") (name "/BATT_MUX_SDL0") (class "Default")
      (node (ref "BATT_MUX") (pin "SDA0") (pinfunction "SDA0_SDA0") (pintype "bidirectional"))
      (node (ref "PICOCLASP1") (pin "P$36") (pinfunction "P$36_P$36") (pintype "bidirectional"))
    )
    (net (code "42") (name "/BATT_MUX_SDL1") (class "Default")
      (node (ref "BATT_MUX") (pin "SDA1") (pinfunction "SDA1_SDA1") (pintype "bidirectional"))
      (node (ref "PICOCLASP1") (pin "P$38") (pinfunction "P$38_P$38") (pintype "bidirectional"))
    )
    (net (code "43") (name "/CPU_STATUS_LED") (class "Default")
      (node (ref "KK396_1") (pin "P$13") (pinfunction "P$13_P$13") (pintype "bidirectional"))
    )
    (net (code "44") (name "/FT232RL_CBUS4") (class "Default")
      (node (ref "IC2") (pin "12") (pinfunction "CBUS4_12") (pintype "bidirectional"))
      (node (ref "U$9") (pin "25") (pinfunction "SHDN_25") (pintype "input"))
    )
    (net (code "45") (name "/FT232RL_CTS") (class "Default")
      (node (ref "IC2") (pin "11") (pinfunction "~{CTS}_11") (pintype "input"))
      (node (ref "U$9") (pin "19") (pinfunction "R5OUT_19") (pintype "output"))
    )
    (net (code "46") (name "/FT232RL_DSR") (class "Default")
      (node (ref "IC2") (pin "9") (pinfunction "~{DSR}_9") (pintype "input"))
      (node (ref "U$9") (pin "22") (pinfunction "R4OUT_22") (pintype "output"))
    )
    (net (code "47") (name "/FT232RL_RXD") (class "Default")
      (node (ref "IC2") (pin "5") (pinfunction "RXD_5") (pintype "input"))
      (node (ref "U$9") (pin "8") (pinfunction "R1OUT_8") (pintype "output"))
    )
    (net (code "48") (name "/FT232RL_TXD") (class "Default")
      (node (ref "IC2") (pin "1") (pinfunction "TXD_1") (pintype "output"))
      (node (ref "U$9") (pin "7") (pinfunction "T1IN_7") (pintype "input"))
    )
    (net (code "49") (name "/FT232RL_~{RESET}") (class "Default")
      (node (ref "IC2") (pin "19") (pinfunction "~{RESET}_19") (pintype "input"))
      (node (ref "R26") (pin "1") (pinfunction "1_1") (pintype "passive"))
      (node (ref "R27") (pin "2") (pinfunction "2_2") (pintype "passive"))
      (node (ref "U$9") (pin "24") (pinfunction "EN_24") (pintype "input"))
    )
    (net (code "50") (name "/GND") (class "Default")
      (node (ref "2PIN_2") (pin "P$2") (pinfunction "P$2_P$2") (pintype "bidirectional"))
      (node (ref "2PIN_3") (pin "P$2") (pinfunction "P$2_P$2") (pintype "bidirectional"))
      (node (ref "2PIN_4") (pin "P$2") (pinfunction "P$2_P$2") (pintype "bidirectional"))
      (node (ref "2PIN_5") (pin "P$2") (pinfunction "P$2_P$2") (pintype "bidirectional"))
      (node (ref "4PIN_5") (pin "P$4") (pinfunction "P$4_P$4") (pintype "bidirectional"))
      (node (ref "6PIN_1") (pin "P$1") (pinfunction "P$1_P$1") (pintype "bidirectional"))
      (node (ref "ARM_BOARD") (pin "1") (pinfunction "P$1_1") (pintype "bidirectional"))
      (node (ref "ARM_BOARD") (pin "10") (pinfunction "P$10_10") (pintype "bidirectional"))
      (node (ref "ARM_BOARD") (pin "13") (pinfunction "P$13_13") (pintype "bidirectional"))
      (node (ref "ARM_BOARD") (pin "16") (pinfunction "P$16_16") (pintype "bidirectional"))
      (node (ref "ARM_BOARD") (pin "19") (pinfunction "P$19_19") (pintype "bidirectional"))
      (node (ref "ARM_BOARD") (pin "24") (pinfunction "P$24_24") (pintype "bidirectional"))
      (node (ref "ARM_BOARD") (pin "28") (pinfunction "P$28_28") (pintype "bidirectional"))
      (node (ref "ARM_BOARD") (pin "32") (pinfunction "P$32_32") (pintype "bidirectional"))
      (node (ref "ARM_BOARD") (pin "36") (pinfunction "P$36_36") (pintype "bidirectional"))
      (node (ref "ARM_BOARD") (pin "4") (pinfunction "P$4_4") (pintype "bidirectional"))
      (node (ref "ARM_BOARD") (pin "40") (pinfunction "P$40_40") (pintype "bidirectional"))
      (node (ref "ARM_BOARD") (pin "41") (pinfunction "P$41_41") (pintype "bidirectional"))
      (node (ref "ARM_BOARD") (pin "45") (pinfunction "P$45_45") (pintype "bidirectional"))
      (node (ref "ARM_BOARD") (pin "48") (pinfunction "P$48_48") (pintype "bidirectional"))
      (node (ref "ARM_BOARD") (pin "50") (pinfunction "P$50_50") (pintype "bidirectional"))
      (node (ref "ARM_BOARD") (pin "54") (pinfunction "P$54_54") (pintype "bidirectional"))
      (node (ref "ARM_BOARD") (pin "57") (pinfunction "P$57_57") (pintype "bidirectional"))
      (node (ref "ARM_BOARD") (pin "59") (pinfunction "P$59_59") (pintype "bidirectional"))
      (node (ref "ARM_BOARD") (pin "60") (pinfunction "P$60_60") (pintype "bidirectional"))
      (node (ref "ARM_BOARD") (pin "64") (pinfunction "P$64_64") (pintype "bidirectional"))
      (node (ref "ARM_BOARD") (pin "66") (pinfunction "P$66_66") (pintype "bidirectional"))
      (node (ref "ARM_BOARD") (pin "69") (pinfunction "P$69_69") (pintype "bidirectional"))
      (node (ref "ARM_BOARD") (pin "7") (pinfunction "P$7_7") (pintype "bidirectional"))
      (node (ref "ARM_BOARD") (pin "73") (pinfunction "P$73_73") (pintype "bidirectional"))
      (node (ref "ARM_BOARD") (pin "75") (pinfunction "P$75_75") (pintype "bidirectional"))
      (node (ref "ARM_BOARD") (pin "78") (pinfunction "P$78_78") (pintype "bidirectional"))
      (node (ref "BATT_MUX") (pin "GND") (pinfunction "GND_GND") (pintype "bidirectional"))
      (node (ref "C1") (pin "2") (pinfunction "2_2") (pintype "passive"))
      (node (ref "C10") (pin "2") (pinfunction "2_2") (pintype "passive"))
      (node (ref "C11") (pin "2") (pinfunction "2_2") (pintype "passive"))
      (node (ref "C12") (pin "1") (pinfunction "1_1") (pintype "passive"))
      (node (ref "C13") (pin "1") (pinfunction "1_1") (pintype "passive"))
      (node (ref "C14") (pin "2") (pinfunction "2_2") (pintype "passive"))
      (node (ref "C2") (pin "2") (pinfunction "2_2") (pintype "passive"))
      (node (ref "C25") (pin "2") (pinfunction "2_2") (pintype "passive"))
      (node (ref "C27") (pin "2") (pinfunction "2_2") (pintype "passive"))
      (node (ref "C29") (pin "2") (pinfunction "2_2") (pintype "passive"))
      (node (ref "C3") (pin "2") (pinfunction "2_2") (pintype "passive"))
      (node (ref "C31") (pin "2") (pinfunction "2_2") (pintype "passive"))
      (node (ref "C33") (pin "2") (pinfunction "2_2") (pintype "passive"))
      (node (ref "C35") (pin "2") (pinfunction "2_2") (pintype "passive"))
      (node (ref "C37") (pin "2") (pinfunction "2_2") (pintype "passive"))
      (node (ref "C39") (pin "2") (pinfunction "2_2") (pintype "passive"))
      (node (ref "C4") (pin "2") (pinfunction "2_2") (pintype "passive"))
      (node (ref "C41") (pin "2") (pinfunction "2_2") (pintype "passive"))
      (node (ref "C42") (pin "2") (pinfunction "2_2") (pintype "passive"))
      (node (ref "C43") (pin "2") (pinfunction "2_2") (pintype "passive"))
      (node (ref "C44") (pin "2") (pinfunction "2_2") (pintype "passive"))
      (node (ref "C45") (pin "2") (pinfunction "2_2") (pintype "passive"))
      (node (ref "C47") (pin "1") (pinfunction "1_1") (pintype "passive"))
      (node (ref "C5") (pin "2") (pinfunction "2_2") (pintype "passive"))
      (node (ref "C6") (pin "2") (pinfunction "2_2") (pintype "passive"))
      (node (ref "C7") (pin "2") (pinfunction "2_2") (pintype "passive"))
      (node (ref "C8") (pin "2") (pinfunction "2_2") (pintype "passive"))
      (node (ref "C9") (pin "2") (pinfunction "2_2") (pintype "passive"))
      (node (ref "G1") (pin "GND") (pinfunction "GND_GND") (pintype "bidirectional"))
      (node (ref "G10") (pin "GND") (pinfunction "GND_GND") (pintype "bidirectional"))
      (node (ref "G11") (pin "GND") (pinfunction "GND_GND") (pintype "bidirectional"))
      (node (ref "G12") (pin "GND") (pinfunction "GND_GND") (pintype "bidirectional"))
      (node (ref "G13") (pin "GND") (pinfunction "GND_GND") (pintype "bidirectional"))
      (node (ref "G14") (pin "GND") (pinfunction "GND_GND") (pintype "bidirectional"))
      (node (ref "G15") (pin "GND") (pinfunction "GND_GND") (pintype "bidirectional"))
      (node (ref "G16") (pin "GND") (pinfunction "GND_GND") (pintype "bidirectional"))
      (node (ref "G2") (pin "GND_A") (pinfunction "GND_A_GND_A") (pintype "power_in"))
      (node (ref "G2") (pin "GND_B") (pinfunction "GND_B_GND_B") (pintype "power_in"))
      (node (ref "G2") (pin "GND_C") (pinfunction "GND_C_GND_C") (pintype "passive"))
      (node (ref "G2") (pin "GND_D") (pinfunction "GND_D_GND_D") (pintype "power_in"))
      (node (ref "G3") (pin "GND_A") (pinfunction "GND_A_GND_A") (pintype "power_in"))
      (node (ref "G3") (pin "GND_B") (pinfunction "GND_B_GND_B") (pintype "power_in"))
      (node (ref "G3") (pin "GND_C") (pinfunction "GND_C_GND_C") (pintype "passive"))
      (node (ref "G3") (pin "GND_D") (pinfunction "GND_D_GND_D") (pintype "power_in"))
      (node (ref "G4") (pin "GND_A") (pinfunction "GND_A_GND_A") (pintype "power_in"))
      (node (ref "G4") (pin "GND_B") (pinfunction "GND_B_GND_B") (pintype "power_in"))
      (node (ref "G4") (pin "GND_C") (pinfunction "GND_C_GND_C") (pintype "passive"))
      (node (ref "G4") (pin "GND_D") (pinfunction "GND_D_GND_D") (pintype "power_in"))
      (node (ref "G5") (pin "2") (pinfunction "GND_2") (pintype "power_in"))
      (node (ref "G5") (pin "TAB") (pinfunction "GND2_TAB") (pintype "power_in"))
      (node (ref "G6") (pin "-") (pinfunction "-_-") (pintype "bidirectional"))
      (node (ref "G7") (pin "-") (pinfunction "-_-") (pintype "bidirectional"))
      (node (ref "G8") (pin "+") (pinfunction "+_+") (pintype "bidirectional"))
      (node (ref "G9") (pin "-") (pinfunction "-_-") (pintype "bidirectional"))
      (node (ref "HDAC1") (pin "P$10") (pinfunction "P$10_P$10") (pintype "bidirectional"))
      (node (ref "HDAC1") (pin "P$12") (pinfunction "P$12_P$12") (pintype "bidirectional"))
      (node (ref "HDAC1") (pin "P$14") (pinfunction "P$14_P$14") (pintype "bidirectional"))
      (node (ref "HDAC1") (pin "P$16") (pinfunction "P$16_P$16") (pintype "bidirectional"))
      (node (ref "HDAC1") (pin "P$2") (pinfunction "P$2_P$2") (pintype "bidirectional"))
      (node (ref "HDAC1") (pin "P$4") (pinfunction "P$4_P$4") (pintype "bidirectional"))
      (node (ref "HDAC1") (pin "P$6") (pinfunction "P$6_P$6") (pintype "bidirectional"))
      (node (ref "HDAC1") (pin "P$8") (pinfunction "P$8_P$8") (pintype "bidirectional"))
      (node (ref "IC2") (pin "18") (pinfunction "GND_18") (pintype "power_in"))
      (node (ref "IC2") (pin "21") (pinfunction "GND_21") (pintype "power_in"))
      (node (ref "IC2") (pin "25") (pinfunction "GND_25") (pintype "power_in"))
      (node (ref "IC2") (pin "26") (pinfunction "TEST_26") (pintype "input"))
      (node (ref "IC2") (pin "7") (pinfunction "GND_7") (pintype "power_in"))
      (node (ref "JMP1") (pin "P$5") (pinfunction "P$5_P$5") (pintype "bidirectional"))
      (node (ref "KK396_1") (pin "P$12") (pinfunction "P$12_P$12") (pintype "bidirectional"))
      (node (ref "KK396_1") (pin "P$14") (pinfunction "P$14_P$14") (pintype "bidirectional"))
      (node (ref "KK396_1") (pin "P$3") (pinfunction "P$3_P$3") (pintype "bidirectional"))
      (node (ref "KK396_1") (pin "P$6") (pinfunction "P$6_P$6") (pintype "bidirectional"))
      (node (ref "KK396_1") (pin "P$9") (pinfunction "P$9_P$9") (pintype "bidirectional"))
      (node (ref "KK396_2") (pin "P$1") (pinfunction "P$1_P$1") (pintype "bidirectional"))
      (node (ref "KK396_2") (pin "P$10") (pinfunction "P$10_P$10") (pintype "bidirectional"))
      (node (ref "KK396_2") (pin "P$4") (pinfunction "P$4_P$4") (pintype "bidirectional"))
      (node (ref "KK396_2") (pin "P$7") (pinfunction "P$7_P$7") (pintype "bidirectional"))
      (node (ref "PICOCLASP1") (pin "P$17") (pinfunction "P$17_P$17") (pintype "bidirectional"))
      (node (ref "PICOCLASP1") (pin "P$22") (pinfunction "P$22_P$22") (pintype "bidirectional"))
      (node (ref "PICOCLASP1") (pin "P$24") (pinfunction "P$24_P$24") (pintype "bidirectional"))
      (node (ref "PICOCLASP1") (pin "P$26") (pinfunction "P$26_P$26") (pintype "bidirectional"))
      (node (ref "PICOCLASP1") (pin "P$27") (pinfunction "P$27_P$27") (pintype "bidirectional"))
      (node (ref "PICOCLASP1") (pin "P$28") (pinfunction "P$28_P$28") (pintype "bidirectional"))
      (node (ref "PICOCLASP1") (pin "P$29") (pinfunction "P$29_P$29") (pintype "bidirectional"))
      (node (ref "PICOCLASP1") (pin "P$30") (pinfunction "P$30_P$30") (pintype "bidirectional"))
      (node (ref "POWER_BOARD") (pin "1") (pinfunction "P$1_1") (pintype "bidirectional"))
      (node (ref "POWER_BOARD") (pin "10") (pinfunction "P$10_10") (pintype "bidirectional"))
      (node (ref "POWER_BOARD") (pin "13") (pinfunction "P$13_13") (pintype "bidirectional"))
      (node (ref "POWER_BOARD") (pin "16") (pinfunction "P$16_16") (pintype "bidirectional"))
      (node (ref "POWER_BOARD") (pin "19") (pinfunction "P$19_19") (pintype "bidirectional"))
      (node (ref "POWER_BOARD") (pin "24") (pinfunction "P$24_24") (pintype "bidirectional"))
      (node (ref "POWER_BOARD") (pin "28") (pinfunction "P$28_28") (pintype "bidirectional"))
      (node (ref "POWER_BOARD") (pin "32") (pinfunction "P$32_32") (pintype "bidirectional"))
      (node (ref "POWER_BOARD") (pin "36") (pinfunction "P$36_36") (pintype "bidirectional"))
      (node (ref "POWER_BOARD") (pin "4") (pinfunction "P$4_4") (pintype "bidirectional"))
      (node (ref "POWER_BOARD") (pin "40") (pinfunction "P$40_40") (pintype "bidirectional"))
      (node (ref "POWER_BOARD") (pin "41") (pinfunction "P$41_41") (pintype "bidirectional"))
      (node (ref "POWER_BOARD") (pin "45") (pinfunction "P$45_45") (pintype "bidirectional"))
      (node (ref "POWER_BOARD") (pin "48") (pinfunction "P$48_48") (pintype "bidirectional"))
      (node (ref "POWER_BOARD") (pin "50") (pinfunction "P$50_50") (pintype "bidirectional"))
      (node (ref "POWER_BOARD") (pin "54") (pinfunction "P$54_54") (pintype "bidirectional"))
      (node (ref "POWER_BOARD") (pin "57") (pinfunction "P$57_57") (pintype "bidirectional"))
      (node (ref "POWER_BOARD") (pin "59") (pinfunction "P$59_59") (pintype "bidirectional"))
      (node (ref "POWER_BOARD") (pin "60") (pinfunction "P$60_60") (pintype "bidirectional"))
      (node (ref "POWER_BOARD") (pin "64") (pinfunction "P$64_64") (pintype "bidirectional"))
      (node (ref "POWER_BOARD") (pin "66") (pinfunction "P$66_66") (pintype "bidirectional"))
      (node (ref "POWER_BOARD") (pin "69") (pinfunction "P$69_69") (pintype "bidirectional"))
      (node (ref "POWER_BOARD") (pin "73") (pinfunction "P$73_73") (pintype "bidirectional"))
      (node (ref "POWER_BOARD") (pin "75") (pinfunction "P$75_75") (pintype "bidirectional"))
      (node (ref "POWER_BOARD") (pin "78") (pinfunction "P$78_78") (pintype "bidirectional"))
      (node (ref "POWER_BOARD") (pin "8") (pinfunction "P$8_8") (pintype "bidirectional"))
      (node (ref "R10") (pin "1") (pinfunction "1_1") (pintype "passive"))
      (node (ref "R11") (pin "1") (pinfunction "1_1") (pintype "passive"))
      (node (ref "R14") (pin "2") (pinfunction "2_2") (pintype "passive"))
      (node (ref "R15") (pin "1") (pinfunction "1_1") (pintype "passive"))
      (node (ref "R16") (pin "2") (pinfunction "2_2") (pintype "passive"))
      (node (ref "R18") (pin "2") (pinfunction "2_2") (pintype "passive"))
      (node (ref "R23") (pin "1") (pinfunction "1_1") (pintype "passive"))
      (node (ref "R24") (pin "1") (pinfunction "1_1") (pintype "passive"))
      (node (ref "R27") (pin "1") (pinfunction "1_1") (pintype "passive"))
      (node (ref "R8") (pin "1") (pinfunction "1_1") (pintype "passive"))
      (node (ref "R9") (pin "1") (pinfunction "1_1") (pintype "passive"))
      (node (ref "SENSOR_BOARD") (pin "1") (pinfunction "P$1_1") (pintype "bidirectional"))
      (node (ref "SENSOR_BOARD") (pin "10") (pinfunction "P$10_10") (pintype "bidirectional"))
      (node (ref "SENSOR_BOARD") (pin "13") (pinfunction "P$13_13") (pintype "bidirectional"))
      (node (ref "SENSOR_BOARD") (pin "16") (pinfunction "P$16_16") (pintype "bidirectional"))
      (node (ref "SENSOR_BOARD") (pin "19") (pinfunction "P$19_19") (pintype "bidirectional"))
      (node (ref "SENSOR_BOARD") (pin "24") (pinfunction "P$24_24") (pintype "bidirectional"))
      (node (ref "SENSOR_BOARD") (pin "28") (pinfunction "P$28_28") (pintype "bidirectional"))
      (node (ref "SENSOR_BOARD") (pin "32") (pinfunction "P$32_32") (pintype "bidirectional"))
      (node (ref "SENSOR_BOARD") (pin "36") (pinfunction "P$36_36") (pintype "bidirectional"))
      (node (ref "SENSOR_BOARD") (pin "4") (pinfunction "P$4_4") (pintype "bidirectional"))
      (node (ref "SENSOR_BOARD") (pin "40") (pinfunction "P$40_40") (pintype "bidirectional"))
      (node (ref "SENSOR_BOARD") (pin "41") (pinfunction "P$41_41") (pintype "bidirectional"))
      (node (ref "SENSOR_BOARD") (pin "45") (pinfunction "P$45_45") (pintype "bidirectional"))
      (node (ref "SENSOR_BOARD") (pin "48") (pinfunction "P$48_48") (pintype "bidirectional"))
      (node (ref "SENSOR_BOARD") (pin "50") (pinfunction "P$50_50") (pintype "bidirectional"))
      (node (ref "SENSOR_BOARD") (pin "54") (pinfunction "P$54_54") (pintype "bidirectional"))
      (node (ref "SENSOR_BOARD") (pin "57") (pinfunction "P$57_57") (pintype "bidirectional"))
      (node (ref "SENSOR_BOARD") (pin "59") (pinfunction "P$59_59") (pintype "bidirectional"))
      (node (ref "SENSOR_BOARD") (pin "60") (pinfunction "P$60_60") (pintype "bidirectional"))
      (node (ref "SENSOR_BOARD") (pin "64") (pinfunction "P$64_64") (pintype "bidirectional"))
      (node (ref "SENSOR_BOARD") (pin "66") (pinfunction "P$66_66") (pintype "bidirectional"))
      (node (ref "SENSOR_BOARD") (pin "69") (pinfunction "P$69_69") (pintype "bidirectional"))
      (node (ref "SENSOR_BOARD") (pin "73") (pinfunction "P$73_73") (pintype "bidirectional"))
      (node (ref "SENSOR_BOARD") (pin "75") (pinfunction "P$75_75") (pintype "bidirectional"))
      (node (ref "SENSOR_BOARD") (pin "78") (pinfunction "P$78_78") (pintype "bidirectional"))
      (node (ref "SENSOR_BOARD") (pin "8") (pinfunction "P$8_8") (pintype "bidirectional"))
      (node (ref "SONAR_BOARD") (pin "1") (pinfunction "P$1_1") (pintype "bidirectional"))
      (node (ref "SONAR_BOARD") (pin "10") (pinfunction "P$10_10") (pintype "bidirectional"))
      (node (ref "SONAR_BOARD") (pin "13") (pinfunction "P$13_13") (pintype "bidirectional"))
      (node (ref "SONAR_BOARD") (pin "16") (pinfunction "P$16_16") (pintype "bidirectional"))
      (node (ref "SONAR_BOARD") (pin "19") (pinfunction "P$19_19") (pintype "bidirectional"))
      (node (ref "SONAR_BOARD") (pin "24") (pinfunction "P$24_24") (pintype "bidirectional"))
      (node (ref "SONAR_BOARD") (pin "28") (pinfunction "P$28_28") (pintype "bidirectional"))
      (node (ref "SONAR_BOARD") (pin "32") (pinfunction "P$32_32") (pintype "bidirectional"))
      (node (ref "SONAR_BOARD") (pin "36") (pinfunction "P$36_36") (pintype "bidirectional"))
      (node (ref "SONAR_BOARD") (pin "4") (pinfunction "P$4_4") (pintype "bidirectional"))
      (node (ref "SONAR_BOARD") (pin "40") (pinfunction "P$40_40") (pintype "bidirectional"))
      (node (ref "SONAR_BOARD") (pin "41") (pinfunction "P$41_41") (pintype "bidirectional"))
      (node (ref "SONAR_BOARD") (pin "45") (pinfunction "P$45_45") (pintype "bidirectional"))
      (node (ref "SONAR_BOARD") (pin "48") (pinfunction "P$48_48") (pintype "bidirectional"))
      (node (ref "SONAR_BOARD") (pin "50") (pinfunction "P$50_50") (pintype "bidirectional"))
      (node (ref "SONAR_BOARD") (pin "54") (pinfunction "P$54_54") (pintype "bidirectional"))
      (node (ref "SONAR_BOARD") (pin "57") (pinfunction "P$57_57") (pintype "bidirectional"))
      (node (ref "SONAR_BOARD") (pin "59") (pinfunction "P$59_59") (pintype "bidirectional"))
      (node (ref "SONAR_BOARD") (pin "60") (pinfunction "P$60_60") (pintype "bidirectional"))
      (node (ref "SONAR_BOARD") (pin "64") (pinfunction "P$64_64") (pintype "bidirectional"))
      (node (ref "SONAR_BOARD") (pin "66") (pinfunction "P$66_66") (pintype "bidirectional"))
      (node (ref "SONAR_BOARD") (pin "69") (pinfunction "P$69_69") (pintype "bidirectional"))
      (node (ref "SONAR_BOARD") (pin "73") (pinfunction "P$73_73") (pintype "bidirectional"))
      (node (ref "SONAR_BOARD") (pin "75") (pinfunction "P$75_75") (pintype "bidirectional"))
      (node (ref "SONAR_BOARD") (pin "78") (pinfunction "P$78_78") (pintype "bidirectional"))
      (node (ref "SONAR_BOARD") (pin "8") (pinfunction "P$8_8") (pintype "bidirectional"))
      (node (ref "THRSTR_CTRL_MUX") (pin "P$12") (pinfunction "GND_P$12") (pintype "power_in"))
      (node (ref "U$1") (pin "P$1") (pinfunction "SOURCE_P$1") (pintype "bidirectional"))
      (node (ref "U$1") (pin "P$2") (pinfunction "SOURCE_P$2") (pintype "bidirectional"))
      (node (ref "U$1") (pin "P$3") (pinfunction "SOURCE_P$3") (pintype "bidirectional"))
      (node (ref "U$2") (pin "P$1") (pinfunction "SOURCE_P$1") (pintype "bidirectional"))
      (node (ref "U$2") (pin "P$2") (pinfunction "SOURCE_P$2") (pintype "bidirectional"))
      (node (ref "U$2") (pin "P$3") (pinfunction "SOURCE_P$3") (pintype "bidirectional"))
      (node (ref "U$3") (pin "P$1") (pinfunction "SOURCE_P$1") (pintype "bidirectional"))
      (node (ref "U$3") (pin "P$2") (pinfunction "SOURCE_P$2") (pintype "bidirectional"))
      (node (ref "U$3") (pin "P$3") (pinfunction "SOURCE_P$3") (pintype "bidirectional"))
      (node (ref "U$4") (pin "P$1") (pinfunction "SOURCE_P$1") (pintype "bidirectional"))
      (node (ref "U$4") (pin "P$2") (pinfunction "SOURCE_P$2") (pintype "bidirectional"))
      (node (ref "U$4") (pin "P$3") (pinfunction "SOURCE_P$3") (pintype "bidirectional"))
      (node (ref "U$5") (pin "P$1") (pinfunction "SOURCE_P$1") (pintype "bidirectional"))
      (node (ref "U$5") (pin "P$2") (pinfunction "SOURCE_P$2") (pintype "bidirectional"))
      (node (ref "U$5") (pin "P$3") (pinfunction "SOURCE_P$3") (pintype "bidirectional"))
      (node (ref "U$6") (pin "P$1") (pinfunction "SOURCE_P$1") (pintype "bidirectional"))
      (node (ref "U$6") (pin "P$2") (pinfunction "SOURCE_P$2") (pintype "bidirectional"))
      (node (ref "U$6") (pin "P$3") (pinfunction "SOURCE_P$3") (pintype "bidirectional"))
      (node (ref "U$7") (pin "P$1") (pinfunction "SOURCE_P$1") (pintype "bidirectional"))
      (node (ref "U$7") (pin "P$2") (pinfunction "SOURCE_P$2") (pintype "bidirectional"))
      (node (ref "U$7") (pin "P$3") (pinfunction "SOURCE_P$3") (pintype "bidirectional"))
      (node (ref "U$8") (pin "P$1") (pinfunction "SOURCE_P$1") (pintype "bidirectional"))
      (node (ref "U$8") (pin "P$2") (pinfunction "SOURCE_P$2") (pintype "bidirectional"))
      (node (ref "U$8") (pin "P$3") (pinfunction "SOURCE_P$3") (pintype "bidirectional"))
      (node (ref "U$9") (pin "10") (pinfunction "GND_10") (pintype "power_in"))
      (node (ref "USB_CONTROLLER") (pin "27") (pinfunction "TSTPLL/48MCLK_27") (pintype "bidirectional"))
      (node (ref "USB_CONTROLLER") (pin "28") (pinfunction "GND_28") (pintype "power_in"))
      (node (ref "USB_CONTROLLER") (pin "31") (pinfunction "TSTMODE_31") (pintype "input"))
      (node (ref "USB_CONTROLLER") (pin "32") (pinfunction "SUSPND_32") (pintype "output"))
      (node (ref "USB_CONTROLLER") (pin "6") (pinfunction "EEDATA/GANGED_6") (pintype "bidirectional"))
      (node (ref "USB_CONTROLLER") (pin "7") (pinfunction "GND_7") (pintype "power_in"))
      (node (ref "USB_CONTROLLER") (pin "8") (pinfunction "BUSPWR_8") (pintype "input"))
      (node (ref "USB_CURRENT") (pin "GND1") (pinfunction "GND1_GND1") (pintype "bidirectional"))
      (node (ref "USB_CURRENT") (pin "GND2") (pinfunction "GND2_GND2") (pintype "bidirectional"))
    )
    (net (code "51") (name "/MISO1") (class "Default")
      (node (ref "6PIN_1") (pin "P$5") (pinfunction "P$5_P$5") (pintype "bidirectional"))
      (node (ref "ARM_BOARD") (pin "23") (pinfunction "P$23_23") (pintype "bidirectional"))
      (node (ref "POWER_BOARD") (pin "23") (pinfunction "P$23_23") (pintype "bidirectional"))
      (node (ref "SENSOR_BOARD") (pin "23") (pinfunction "P$23_23") (pintype "bidirectional"))
      (node (ref "SONAR_BOARD") (pin "23") (pinfunction "P$23_23") (pintype "bidirectional"))
    )
    (net (code "52") (name "/MISO2") (class "Default")
      (node (ref "ARM_BOARD") (pin "27") (pinfunction "P$27_27") (pintype "bidirectional"))
      (node (ref "POWER_BOARD") (pin "7") (pinfunction "P$7_7") (pintype "bidirectional"))
      (node (ref "SENSOR_BOARD") (pin "7") (pinfunction "P$7_7") (pintype "bidirectional"))
      (node (ref "SONAR_BOARD") (pin "7") (pinfunction "P$7_7") (pintype "bidirectional"))
    )
    (net (code "53") (name "/MOSI1") (class "Default")
      (node (ref "6PIN_1") (pin "P$6") (pinfunction "P$6_P$6") (pintype "bidirectional"))
      (node (ref "ARM_BOARD") (pin "22") (pinfunction "P$22_22") (pintype "bidirectional"))
      (node (ref "POWER_BOARD") (pin "22") (pinfunction "P$22_22") (pintype "bidirectional"))
      (node (ref "SENSOR_BOARD") (pin "22") (pinfunction "P$22_22") (pintype "bidirectional"))
      (node (ref "SONAR_BOARD") (pin "22") (pinfunction "P$22_22") (pintype "bidirectional"))
    )
    (net (code "54") (name "/MOSI2") (class "Default")
      (node (ref "ARM_BOARD") (pin "26") (pinfunction "P$26_26") (pintype "bidirectional"))
      (node (ref "POWER_BOARD") (pin "6") (pinfunction "P$6_6") (pintype "bidirectional"))
      (node (ref "SENSOR_BOARD") (pin "6") (pinfunction "P$6_6") (pintype "bidirectional"))
      (node (ref "SONAR_BOARD") (pin "6") (pinfunction "P$6_6") (pintype "bidirectional"))
    )
    (net (code "55") (name "/PERIPH_RESET") (class "Default")
      (node (ref "ARM_BOARD") (pin "9") (pinfunction "P$9_9") (pintype "bidirectional"))
      (node (ref "POWER_BOARD") (pin "9") (pinfunction "P$9_9") (pintype "bidirectional"))
      (node (ref "R20") (pin "2") (pinfunction "2_2") (pintype "passive"))
      (node (ref "SENSOR_BOARD") (pin "9") (pinfunction "P$9_9") (pintype "bidirectional"))
      (node (ref "SONAR_BOARD") (pin "9") (pinfunction "P$9_9") (pintype "bidirectional"))
      (node (ref "THRSTR_CTRL_MUX") (pin "P$3") (pinfunction "~{RESET}_P$3") (pintype "input"))
      (node (ref "USB_CONTROLLER") (pin "4") (pinfunction "~{RESET}_4") (pintype "input"))
    )
    (net (code "56") (name "/PWR_DEBUG") (class "Default")
      (node (ref "4PIN_5") (pin "P$3") (pinfunction "P$3_P$3") (pintype "bidirectional"))
    )
    (net (code "57") (name "/RX") (class "Default")
      (node (ref "ARM_BOARD") (pin "76") (pinfunction "P$76_76") (pintype "bidirectional"))
      (node (ref "POWER_BOARD") (pin "76") (pinfunction "P$76_76") (pintype "bidirectional"))
      (node (ref "SENSOR_BOARD") (pin "76") (pinfunction "P$76_76") (pintype "bidirectional"))
      (node (ref "SONAR_BOARD") (pin "76") (pinfunction "P$76_76") (pintype "bidirectional"))
    )
    (net (code "58") (name "/RX_CPU") (class "Default")
      (node (ref "KK396_1") (pin "P$7") (pinfunction "P$7_P$7") (pintype "bidirectional"))
      (node (ref "U$9") (pin "4") (pinfunction "R2IN_4") (pintype "input"))
    )
    (net (code "59") (name "/RX_CPU_OUT") (class "Default")
      (node (ref "ARM_BOARD") (pin "14") (pinfunction "P$14_14") (pintype "bidirectional"))
      (node (ref "POWER_BOARD") (pin "14") (pinfunction "P$14_14") (pintype "bidirectional"))
      (node (ref "SENSOR_BOARD") (pin "14") (pinfunction "P$14_14") (pintype "bidirectional"))
      (node (ref "SONAR_BOARD") (pin "14") (pinfunction "P$14_14") (pintype "bidirectional"))
      (node (ref "U$9") (pin "5") (pinfunction "R2OUT_5") (pintype "output"))
    )
    (net (code "60") (name "/RX_DEBUG") (class "Default")
      (node (ref "KK396_1") (pin "P$4") (pinfunction "P$4_P$4") (pintype "bidirectional"))
      (node (ref "U$9") (pin "27") (pinfunction "R3IN_27") (pintype "input"))
    )
    (net (code "61") (name "/RX_DEBUG_OUT") (class "Default")
      (node (ref "4PIN_5") (pin "P$1") (pinfunction "P$1_P$1") (pintype "bidirectional"))
      (node (ref "ARM_BOARD") (pin "17") (pinfunction "P$17_17") (pintype "bidirectional"))
      (node (ref "POWER_BOARD") (pin "17") (pinfunction "P$17_17") (pintype "bidirectional"))
      (node (ref "SENSOR_BOARD") (pin "17") (pinfunction "P$17_17") (pintype "bidirectional"))
      (node (ref "SONAR_BOARD") (pin "17") (pinfunction "P$17_17") (pintype "bidirectional"))
      (node (ref "U$9") (pin "26") (pinfunction "R3OUT_26") (pintype "output"))
    )
    (net (code "62") (name "/RX_DVL") (class "Default")
      (node (ref "PICOCLASP1") (pin "P$31") (pinfunction "P$31_P$31") (pintype "bidirectional"))
      (node (ref "U$9") (pin "9") (pinfunction "R1IN_9") (pintype "input"))
    )
    (net (code "63") (name "/RX_IMU") (class "Default")
      (node (ref "KK396_2") (pin "P$15") (pinfunction "P$15_P$15") (pintype "bidirectional"))
      (node (ref "PICOCLASP1") (pin "P$33") (pinfunction "P$33_P$33") (pintype "bidirectional"))
    )
    (net (code "64") (name "/SCK1") (class "Default")
      (node (ref "6PIN_1") (pin "P$3") (pinfunction "P$3_P$3") (pintype "bidirectional"))
      (node (ref "ARM_BOARD") (pin "21") (pinfunction "P$21_21") (pintype "bidirectional"))
      (node (ref "POWER_BOARD") (pin "21") (pinfunction "P$21_21") (pintype "bidirectional"))
      (node (ref "SENSOR_BOARD") (pin "21") (pinfunction "P$21_21") (pintype "bidirectional"))
      (node (ref "SONAR_BOARD") (pin "21") (pinfunction "P$21_21") (pintype "bidirectional"))
    )
    (net (code "65") (name "/SCK2") (class "Default")
      (node (ref "ARM_BOARD") (pin "25") (pinfunction "P$25_25") (pintype "bidirectional"))
      (node (ref "POWER_BOARD") (pin "5") (pinfunction "P$5_5") (pintype "bidirectional"))
      (node (ref "SENSOR_BOARD") (pin "5") (pinfunction "P$5_5") (pintype "bidirectional"))
      (node (ref "SONAR_BOARD") (pin "5") (pinfunction "P$5_5") (pintype "bidirectional"))
    )
    (net (code "66") (name "/SCL1_BUF") (class "Default")
      (node (ref "ARM_BOARD") (pin "3") (pinfunction "P$3_3") (pintype "bidirectional"))
      (node (ref "BATT_MUX") (pin "SCL") (pinfunction "SCL_SCL") (pintype "bidirectional"))
      (node (ref "JMP1") (pin "P$7") (pinfunction "P$7_P$7") (pintype "bidirectional"))
      (node (ref "POWER_BOARD") (pin "3") (pinfunction "P$3_3") (pintype "bidirectional"))
      (node (ref "SENSOR_BOARD") (pin "3") (pinfunction "P$3_3") (pintype "bidirectional"))
      (node (ref "SONAR_BOARD") (pin "3") (pinfunction "P$3_3") (pintype "bidirectional"))
    )
    (net (code "67") (name "/SCL1_UNBUF") (class "Default")
      (node (ref "ARM_BOARD") (pin "12") (pinfunction "P$12_12") (pintype "bidirectional"))
      (node (ref "POWER_BOARD") (pin "12") (pinfunction "P$12_12") (pintype "bidirectional"))
      (node (ref "SENSOR_BOARD") (pin "12") (pinfunction "P$12_12") (pintype "bidirectional"))
      (node (ref "SONAR_BOARD") (pin "12") (pinfunction "P$12_12") (pintype "bidirectional"))
      (node (ref "THRSTR_CTRL_MUX") (pin "P$21") (pinfunction "SCL_P$21") (pintype "input"))
    )
    (net (code "68") (name "/SDL1_BUF") (class "Default")
      (node (ref "ARM_BOARD") (pin "2") (pinfunction "P$2_2") (pintype "bidirectional"))
      (node (ref "BATT_MUX") (pin "SDA") (pinfunction "SDA_SDA") (pintype "bidirectional"))
      (node (ref "JMP1") (pin "P$8") (pinfunction "P$8_P$8") (pintype "bidirectional"))
      (node (ref "POWER_BOARD") (pin "2") (pinfunction "P$2_2") (pintype "bidirectional"))
      (node (ref "R21") (pin "2") (pinfunction "2_2") (pintype "passive"))
      (node (ref "SENSOR_BOARD") (pin "2") (pinfunction "P$2_2") (pintype "bidirectional"))
      (node (ref "SONAR_BOARD") (pin "2") (pinfunction "P$2_2") (pintype "bidirectional"))
    )
    (net (code "69") (name "/SDL1_UNBUF") (class "Default")
      (node (ref "ARM_BOARD") (pin "11") (pinfunction "P$11_11") (pintype "bidirectional"))
      (node (ref "POWER_BOARD") (pin "11") (pinfunction "P$11_11") (pintype "bidirectional"))
      (node (ref "R22") (pin "2") (pinfunction "2_2") (pintype "passive"))
      (node (ref "SENSOR_BOARD") (pin "11") (pinfunction "P$11_11") (pintype "bidirectional"))
      (node (ref "SONAR_BOARD") (pin "11") (pinfunction "P$11_11") (pintype "bidirectional"))
      (node (ref "THRSTR_CTRL_MUX") (pin "P$22") (pinfunction "SDL_P$22") (pintype "input"))
    )
    (net (code "70") (name "/THRSTR_CTRL_A0") (class "Default")
      (node (ref "ARM_BOARD") (pin "5") (pinfunction "P$5_5") (pintype "bidirectional"))
      (node (ref "THRSTR_CTRL_MUX") (pin "P$1") (pinfunction "A0_P$1") (pintype "input"))
    )
    (net (code "71") (name "/THRSTR_CTRL_A1") (class "Default")
      (node (ref "ARM_BOARD") (pin "6") (pinfunction "P$6_6") (pintype "bidirectional"))
      (node (ref "THRSTR_CTRL_MUX") (pin "P$2") (pinfunction "A1_P$2") (pintype "input"))
    )
    (net (code "72") (name "/THRSTR_CTRL_A2") (class "Default")
      (node (ref "ARM_BOARD") (pin "8") (pinfunction "P$8_8") (pintype "bidirectional"))
      (node (ref "THRSTR_CTRL_MUX") (pin "P$23") (pinfunction "A2_P$23") (pintype "input"))
    )
    (net (code "73") (name "/THRSTR_CTRL_SC0") (class "Default")
      (node (ref "PICOCLASP1") (pin "P$2") (pinfunction "P$2_P$2") (pintype "bidirectional"))
      (node (ref "THRSTR_CTRL_MUX") (pin "P$5") (pinfunction "SC0_P$5") (pintype "output"))
    )
    (net (code "74") (name "/THRSTR_CTRL_SC1") (class "Default")
      (node (ref "PICOCLASP1") (pin "P$4") (pinfunction "P$4_P$4") (pintype "bidirectional"))
      (node (ref "THRSTR_CTRL_MUX") (pin "P$7") (pinfunction "SC1_P$7") (pintype "output"))
    )
    (net (code "75") (name "/THRSTR_CTRL_SC2") (class "Default")
      (node (ref "PICOCLASP1") (pin "P$6") (pinfunction "P$6_P$6") (pintype "bidirectional"))
      (node (ref "THRSTR_CTRL_MUX") (pin "P$9") (pinfunction "SC2_P$9") (pintype "output"))
    )
    (net (code "76") (name "/THRSTR_CTRL_SC3") (class "Default")
      (node (ref "PICOCLASP1") (pin "P$8") (pinfunction "P$8_P$8") (pintype "bidirectional"))
      (node (ref "THRSTR_CTRL_MUX") (pin "P$11") (pinfunction "SC3_P$11") (pintype "output"))
    )
    (net (code "77") (name "/THRSTR_CTRL_SC4") (class "Default")
      (node (ref "PICOCLASP1") (pin "P$10") (pinfunction "P$10_P$10") (pintype "bidirectional"))
      (node (ref "THRSTR_CTRL_MUX") (pin "P$14") (pinfunction "SC4_P$14") (pintype "output"))
    )
    (net (code "78") (name "/THRSTR_CTRL_SC5") (class "Default")
      (node (ref "PICOCLASP1") (pin "P$12") (pinfunction "P$12_P$12") (pintype "bidirectional"))
      (node (ref "THRSTR_CTRL_MUX") (pin "P$16") (pinfunction "SC5_P$16") (pintype "output"))
    )
    (net (code "79") (name "/THRSTR_CTRL_SC6") (class "Default")
      (node (ref "PICOCLASP1") (pin "P$14") (pinfunction "P$14_P$14") (pintype "bidirectional"))
      (node (ref "THRSTR_CTRL_MUX") (pin "P$18") (pinfunction "SC6_P$18") (pintype "output"))
    )
    (net (code "80") (name "/THRSTR_CTRL_SC7") (class "Default")
      (node (ref "PICOCLASP1") (pin "P$16") (pinfunction "P$16_P$16") (pintype "bidirectional"))
      (node (ref "THRSTR_CTRL_MUX") (pin "P$20") (pinfunction "SC7_P$20") (pintype "output"))
    )
    (net (code "81") (name "/THRSTR_CTRL_SD0") (class "Default")
      (node (ref "PICOCLASP1") (pin "P$1") (pinfunction "P$1_P$1") (pintype "bidirectional"))
      (node (ref "THRSTR_CTRL_MUX") (pin "P$4") (pinfunction "SD0_P$4") (pintype "output"))
    )
    (net (code "82") (name "/THRSTR_CTRL_SD1") (class "Default")
      (node (ref "PICOCLASP1") (pin "P$3") (pinfunction "P$3_P$3") (pintype "bidirectional"))
      (node (ref "THRSTR_CTRL_MUX") (pin "P$6") (pinfunction "SD1_P$6") (pintype "output"))
    )
    (net (code "83") (name "/THRSTR_CTRL_SD2") (class "Default")
      (node (ref "PICOCLASP1") (pin "P$5") (pinfunction "P$5_P$5") (pintype "bidirectional"))
      (node (ref "THRSTR_CTRL_MUX") (pin "P$8") (pinfunction "SD2_P$8") (pintype "output"))
    )
    (net (code "84") (name "/THRSTR_CTRL_SD3") (class "Default")
      (node (ref "PICOCLASP1") (pin "P$7") (pinfunction "P$7_P$7") (pintype "bidirectional"))
      (node (ref "THRSTR_CTRL_MUX") (pin "P$10") (pinfunction "SD3_P$10") (pintype "output"))
    )
    (net (code "85") (name "/THRSTR_CTRL_SD4") (class "Default")
      (node (ref "PICOCLASP1") (pin "P$9") (pinfunction "P$9_P$9") (pintype "bidirectional"))
      (node (ref "THRSTR_CTRL_MUX") (pin "P$13") (pinfunction "SD4_P$13") (pintype "output"))
    )
    (net (code "86") (name "/THRSTR_CTRL_SD5") (class "Default")
      (node (ref "PICOCLASP1") (pin "P$11") (pinfunction "P$11_P$11") (pintype "bidirectional"))
      (node (ref "THRSTR_CTRL_MUX") (pin "P$15") (pinfunction "SD5_P$15") (pintype "output"))
    )
    (net (code "87") (name "/THRSTR_CTRL_SD6") (class "Default")
      (node (ref "PICOCLASP1") (pin "P$13") (pinfunction "P$13_P$13") (pintype "bidirectional"))
      (node (ref "THRSTR_CTRL_MUX") (pin "P$17") (pinfunction "SD6_P$17") (pintype "output"))
    )
    (net (code "88") (name "/THRSTR_CTRL_SD7") (class "Default")
      (node (ref "PICOCLASP1") (pin "P$15") (pinfunction "P$15_P$15") (pintype "bidirectional"))
      (node (ref "THRSTR_CTRL_MUX") (pin "P$19") (pinfunction "SD7_P$19") (pintype "output"))
    )
    (net (code "89") (name "/THRSTR_PWR1+") (class "Default")
      (node (ref "G1") (pin "IP+1") (pinfunction "IP+_IP+1") (pintype "bidirectional"))
      (node (ref "G1") (pin "IP+2") (pinfunction "IP+_IP+2") (pintype "bidirectional"))
      (node (ref "HDAC1") (pin "P$1") (pinfunction "P$1_P$1") (pintype "bidirectional"))
    )
    (net (code "90") (name "/THRSTR_PWR1-") (class "Default")
      (node (ref "G1") (pin "IP-1") (pinfunction "IP-_IP-1") (pintype "bidirectional"))
      (node (ref "G1") (pin "IP-2") (pinfunction "IP-_IP-2") (pintype "bidirectional"))
      (node (ref "U$1") (pin "P$5") (pinfunction "DRAIN_P$5") (pintype "bidirectional"))
      (node (ref "U$1") (pin "P$6") (pinfunction "DRAIN_P$6") (pintype "bidirectional"))
      (node (ref "U$1") (pin "P$7") (pinfunction "DRAIN_P$7") (pintype "bidirectional"))
      (node (ref "U$1") (pin "P$8") (pinfunction "DRAIN_P$8") (pintype "bidirectional"))
    )
    (net (code "91") (name "/THRSTR_PWR2+") (class "Default")
      (node (ref "G10") (pin "IP+1") (pinfunction "IP+_IP+1") (pintype "bidirectional"))
      (node (ref "G10") (pin "IP+2") (pinfunction "IP+_IP+2") (pintype "bidirectional"))
      (node (ref "HDAC1") (pin "P$3") (pinfunction "P$3_P$3") (pintype "bidirectional"))
    )
    (net (code "92") (name "/THRSTR_PWR2-") (class "Default")
      (node (ref "G10") (pin "IP-1") (pinfunction "IP-_IP-1") (pintype "bidirectional"))
      (node (ref "G10") (pin "IP-2") (pinfunction "IP-_IP-2") (pintype "bidirectional"))
      (node (ref "U$2") (pin "P$5") (pinfunction "DRAIN_P$5") (pintype "bidirectional"))
      (node (ref "U$2") (pin "P$6") (pinfunction "DRAIN_P$6") (pintype "bidirectional"))
      (node (ref "U$2") (pin "P$7") (pinfunction "DRAIN_P$7") (pintype "bidirectional"))
      (node (ref "U$2") (pin "P$8") (pinfunction "DRAIN_P$8") (pintype "bidirectional"))
    )
    (net (code "93") (name "/THRSTR_PWR3+") (class "Default")
      (node (ref "G11") (pin "IP+1") (pinfunction "IP+_IP+1") (pintype "bidirectional"))
      (node (ref "G11") (pin "IP+2") (pinfunction "IP+_IP+2") (pintype "bidirectional"))
      (node (ref "HDAC1") (pin "P$5") (pinfunction "P$5_P$5") (pintype "bidirectional"))
    )
    (net (code "94") (name "/THRSTR_PWR3-") (class "Default")
      (node (ref "G11") (pin "IP-1") (pinfunction "IP-_IP-1") (pintype "bidirectional"))
      (node (ref "G11") (pin "IP-2") (pinfunction "IP-_IP-2") (pintype "bidirectional"))
      (node (ref "U$3") (pin "P$5") (pinfunction "DRAIN_P$5") (pintype "bidirectional"))
      (node (ref "U$3") (pin "P$6") (pinfunction "DRAIN_P$6") (pintype "bidirectional"))
      (node (ref "U$3") (pin "P$7") (pinfunction "DRAIN_P$7") (pintype "bidirectional"))
      (node (ref "U$3") (pin "P$8") (pinfunction "DRAIN_P$8") (pintype "bidirectional"))
    )
    (net (code "95") (name "/THRSTR_PWR4+") (class "Default")
      (node (ref "G12") (pin "IP+1") (pinfunction "IP+_IP+1") (pintype "bidirectional"))
      (node (ref "G12") (pin "IP+2") (pinfunction "IP+_IP+2") (pintype "bidirectional"))
      (node (ref "HDAC1") (pin "P$7") (pinfunction "P$7_P$7") (pintype "bidirectional"))
    )
    (net (code "96") (name "/THRSTR_PWR4-") (class "Default")
      (node (ref "G12") (pin "IP-1") (pinfunction "IP-_IP-1") (pintype "bidirectional"))
      (node (ref "G12") (pin "IP-2") (pinfunction "IP-_IP-2") (pintype "bidirectional"))
      (node (ref "U$4") (pin "P$5") (pinfunction "DRAIN_P$5") (pintype "bidirectional"))
      (node (ref "U$4") (pin "P$6") (pinfunction "DRAIN_P$6") (pintype "bidirectional"))
      (node (ref "U$4") (pin "P$7") (pinfunction "DRAIN_P$7") (pintype "bidirectional"))
      (node (ref "U$4") (pin "P$8") (pinfunction "DRAIN_P$8") (pintype "bidirectional"))
    )
    (net (code "97") (name "/THRSTR_PWR5+") (class "Default")
      (node (ref "G13") (pin "IP+1") (pinfunction "IP+_IP+1") (pintype "bidirectional"))
      (node (ref "G13") (pin "IP+2") (pinfunction "IP+_IP+2") (pintype "bidirectional"))
      (node (ref "HDAC1") (pin "P$9") (pinfunction "P$9_P$9") (pintype "bidirectional"))
    )
    (net (code "98") (name "/THRSTR_PWR5-") (class "Default")
      (node (ref "G13") (pin "IP-1") (pinfunction "IP-_IP-1") (pintype "bidirectional"))
      (node (ref "G13") (pin "IP-2") (pinfunction "IP-_IP-2") (pintype "bidirectional"))
      (node (ref "U$8") (pin "P$5") (pinfunction "DRAIN_P$5") (pintype "bidirectional"))
      (node (ref "U$8") (pin "P$6") (pinfunction "DRAIN_P$6") (pintype "bidirectional"))
      (node (ref "U$8") (pin "P$7") (pinfunction "DRAIN_P$7") (pintype "bidirectional"))
      (node (ref "U$8") (pin "P$8") (pinfunction "DRAIN_P$8") (pintype "bidirectional"))
    )
    (net (code "99") (name "/THRSTR_PWR6+") (class "Default")
      (node (ref "G14") (pin "IP+1") (pinfunction "IP+_IP+1") (pintype "bidirectional"))
      (node (ref "G14") (pin "IP+2") (pinfunction "IP+_IP+2") (pintype "bidirectional"))
      (node (ref "HDAC1") (pin "P$11") (pinfunction "P$11_P$11") (pintype "bidirectional"))
    )
    (net (code "100") (name "/THRSTR_PWR6-") (class "Default")
      (node (ref "G14") (pin "IP-1") (pinfunction "IP-_IP-1") (pintype "bidirectional"))
      (node (ref "G14") (pin "IP-2") (pinfunction "IP-_IP-2") (pintype "bidirectional"))
      (node (ref "U$7") (pin "P$5") (pinfunction "DRAIN_P$5") (pintype "bidirectional"))
      (node (ref "U$7") (pin "P$6") (pinfunction "DRAIN_P$6") (pintype "bidirectional"))
      (node (ref "U$7") (pin "P$7") (pinfunction "DRAIN_P$7") (pintype "bidirectional"))
      (node (ref "U$7") (pin "P$8") (pinfunction "DRAIN_P$8") (pintype "bidirectional"))
    )
    (net (code "101") (name "/THRSTR_PWR7+") (class "Default")
      (node (ref "G15") (pin "IP+1") (pinfunction "IP+_IP+1") (pintype "bidirectional"))
      (node (ref "G15") (pin "IP+2") (pinfunction "IP+_IP+2") (pintype "bidirectional"))
      (node (ref "HDAC1") (pin "P$13") (pinfunction "P$13_P$13") (pintype "bidirectional"))
    )
    (net (code "102") (name "/THRSTR_PWR7-") (class "Default")
      (node (ref "G15") (pin "IP-1") (pinfunction "IP-_IP-1") (pintype "bidirectional"))
      (node (ref "G15") (pin "IP-2") (pinfunction "IP-_IP-2") (pintype "bidirectional"))
      (node (ref "U$6") (pin "P$5") (pinfunction "DRAIN_P$5") (pintype "bidirectional"))
      (node (ref "U$6") (pin "P$6") (pinfunction "DRAIN_P$6") (pintype "bidirectional"))
      (node (ref "U$6") (pin "P$7") (pinfunction "DRAIN_P$7") (pintype "bidirectional"))
      (node (ref "U$6") (pin "P$8") (pinfunction "DRAIN_P$8") (pintype "bidirectional"))
    )
    (net (code "103") (name "/THRSTR_PWR8+") (class "Default")
      (node (ref "G16") (pin "IP+1") (pinfunction "IP+_IP+1") (pintype "bidirectional"))
      (node (ref "G16") (pin "IP+2") (pinfunction "IP+_IP+2") (pintype "bidirectional"))
      (node (ref "HDAC1") (pin "P$15") (pinfunction "P$15_P$15") (pintype "bidirectional"))
    )
    (net (code "104") (name "/THRSTR_PWR8-") (class "Default")
      (node (ref "G16") (pin "IP-1") (pinfunction "IP-_IP-1") (pintype "bidirectional"))
      (node (ref "G16") (pin "IP-2") (pinfunction "IP-_IP-2") (pintype "bidirectional"))
      (node (ref "U$5") (pin "P$5") (pinfunction "DRAIN_P$5") (pintype "bidirectional"))
      (node (ref "U$5") (pin "P$6") (pinfunction "DRAIN_P$6") (pintype "bidirectional"))
      (node (ref "U$5") (pin "P$7") (pinfunction "DRAIN_P$7") (pintype "bidirectional"))
      (node (ref "U$5") (pin "P$8") (pinfunction "DRAIN_P$8") (pintype "bidirectional"))
    )
    (net (code "105") (name "/THRSTR_PWR_GATE") (class "Default")
      (node (ref "R23") (pin "2") (pinfunction "2_2") (pintype "passive"))
      (node (ref "THRUSTER_PWR_SWTICH") (pin "P$2") (pinfunction "P$2_P$2") (pintype "bidirectional"))
      (node (ref "U$1") (pin "P$4") (pinfunction "GATE_P$4") (pintype "bidirectional"))
      (node (ref "U$2") (pin "P$4") (pinfunction "GATE_P$4") (pintype "bidirectional"))
      (node (ref "U$3") (pin "P$4") (pinfunction "GATE_P$4") (pintype "bidirectional"))
      (node (ref "U$4") (pin "P$4") (pinfunction "GATE_P$4") (pintype "bidirectional"))
      (node (ref "U$5") (pin "P$4") (pinfunction "GATE_P$4") (pintype "bidirectional"))
      (node (ref "U$6") (pin "P$4") (pinfunction "GATE_P$4") (pintype "bidirectional"))
      (node (ref "U$7") (pin "P$4") (pinfunction "GATE_P$4") (pintype "bidirectional"))
      (node (ref "U$8") (pin "P$4") (pinfunction "GATE_P$4") (pintype "bidirectional"))
    )
    (net (code "106") (name "/TX") (class "Default")
      (node (ref "ARM_BOARD") (pin "77") (pinfunction "P$77_77") (pintype "bidirectional"))
      (node (ref "POWER_BOARD") (pin "77") (pinfunction "P$77_77") (pintype "bidirectional"))
      (node (ref "SENSOR_BOARD") (pin "77") (pinfunction "P$77_77") (pintype "bidirectional"))
      (node (ref "SONAR_BOARD") (pin "77") (pinfunction "P$77_77") (pintype "bidirectional"))
    )
    (net (code "107") (name "/TX_CPU") (class "Default")
      (node (ref "KK396_1") (pin "P$8") (pinfunction "P$8_P$8") (pintype "bidirectional"))
      (node (ref "U$9") (pin "6") (pinfunction "T2IN_6") (pintype "input"))
    )
    (net (code "108") (name "/TX_CPU_OUT") (class "Default")
      (node (ref "ARM_BOARD") (pin "15") (pinfunction "P$15_15") (pintype "bidirectional"))
      (node (ref "POWER_BOARD") (pin "15") (pinfunction "P$15_15") (pintype "bidirectional"))
      (node (ref "SENSOR_BOARD") (pin "15") (pinfunction "P$15_15") (pintype "bidirectional"))
      (node (ref "SONAR_BOARD") (pin "15") (pinfunction "P$15_15") (pintype "bidirectional"))
      (node (ref "U$9") (pin "3") (pinfunction "T2OUT_3") (pintype "output"))
    )
    (net (code "109") (name "/TX_DEBUG") (class "Default")
      (node (ref "KK396_1") (pin "P$5") (pinfunction "P$5_P$5") (pintype "bidirectional"))
      (node (ref "U$9") (pin "20") (pinfunction "T3IN_20") (pintype "input"))
    )
    (net (code "110") (name "/TX_DEBUG_OUT") (class "Default")
      (node (ref "4PIN_5") (pin "P$2") (pinfunction "P$2_P$2") (pintype "bidirectional"))
      (node (ref "ARM_BOARD") (pin "18") (pinfunction "P$18_18") (pintype "bidirectional"))
      (node (ref "POWER_BOARD") (pin "18") (pinfunction "P$18_18") (pintype "bidirectional"))
      (node (ref "SENSOR_BOARD") (pin "18") (pinfunction "P$18_18") (pintype "bidirectional"))
      (node (ref "SONAR_BOARD") (pin "18") (pinfunction "P$18_18") (pintype "bidirectional"))
      (node (ref "U$9") (pin "1") (pinfunction "T3OUT_1") (pintype "output"))
    )
    (net (code "111") (name "/TX_DVL") (class "Default")
      (node (ref "PICOCLASP1") (pin "P$32") (pinfunction "P$32_P$32") (pintype "bidirectional"))
      (node (ref "U$9") (pin "2") (pinfunction "T1OUT_2") (pintype "output"))
    )
    (net (code "112") (name "/TX_IMU") (class "Default")
      (node (ref "KK396_2") (pin "P$14") (pinfunction "P$14_P$14") (pintype "bidirectional"))
      (node (ref "PICOCLASP1") (pin "P$34") (pinfunction "P$34_P$34") (pintype "bidirectional"))
    )
    (net (code "113") (name "/USB_1M") (class "Default")
      (node (ref "G2") (pin "A") (pinfunction "A_A") (pintype "bidirectional"))
      (node (ref "R4") (pin "1") (pinfunction "1_1") (pintype "passive"))
      (node (ref "R8") (pin "2") (pinfunction "2_2") (pintype "passive"))
    )
    (net (code "114") (name "/USB_1P") (class "Default")
      (node (ref "G2") (pin "B") (pinfunction "B_B") (pintype "bidirectional"))
      (node (ref "R5") (pin "1") (pinfunction "1_1") (pintype "passive"))
      (node (ref "R9") (pin "2") (pinfunction "2_2") (pintype "passive"))
    )
    (net (code "115") (name "/USB_2M") (class "Default")
      (node (ref "G2") (pin "C") (pinfunction "C_C") (pintype "bidirectional"))
      (node (ref "R10") (pin "2") (pinfunction "2_2") (pintype "passive"))
      (node (ref "R6") (pin "1") (pinfunction "1_1") (pintype "passive"))
    )
    (net (code "116") (name "/USB_2P") (class "Default")
      (node (ref "G2") (pin "D") (pinfunction "D_D") (pintype "bidirectional"))
      (node (ref "R11") (pin "2") (pinfunction "2_2") (pintype "passive"))
      (node (ref "R7") (pin "1") (pinfunction "1_1") (pintype "passive"))
    )
    (net (code "117") (name "/USB_3M") (class "Default")
      (node (ref "G3") (pin "A") (pinfunction "A_A") (pintype "bidirectional"))
      (node (ref "POWER_BOARD") (pin "80") (pinfunction "P$80_80") (pintype "bidirectional"))
      (node (ref "R19") (pin "1") (pinfunction "1_1") (pintype "passive"))
      (node (ref "SENSOR_BOARD") (pin "80") (pinfunction "P$80_80") (pintype "bidirectional"))
      (node (ref "SONAR_BOARD") (pin "80") (pinfunction "P$80_80") (pintype "bidirectional"))
    )
    (net (code "118") (name "/USB_3P") (class "Default")
      (node (ref "G3") (pin "B") (pinfunction "B_B") (pintype "bidirectional"))
      (node (ref "POWER_BOARD") (pin "79") (pinfunction "P$79_79") (pintype "bidirectional"))
      (node (ref "R17") (pin "2") (pinfunction "2_2") (pintype "passive"))
      (node (ref "SENSOR_BOARD") (pin "79") (pinfunction "P$79_79") (pintype "bidirectional"))
      (node (ref "SONAR_BOARD") (pin "79") (pinfunction "P$79_79") (pintype "bidirectional"))
    )
    (net (code "119") (name "/USB_4M") (class "Default")
      (node (ref "ARM_BOARD") (pin "80") (pinfunction "P$80_80") (pintype "bidirectional"))
      (node (ref "G3") (pin "C") (pinfunction "C_C") (pintype "bidirectional"))
      (node (ref "R13") (pin "1") (pinfunction "1_1") (pintype "passive"))
      (node (ref "R15") (pin "2") (pinfunction "2_2") (pintype "passive"))
    )
    (net (code "120") (name "/USB_4P") (class "Default")
      (node (ref "ARM_BOARD") (pin "79") (pinfunction "P$79_79") (pintype "bidirectional"))
      (node (ref "G3") (pin "D") (pinfunction "D_D") (pintype "bidirectional"))
      (node (ref "R12") (pin "2") (pinfunction "2_2") (pintype "passive"))
      (node (ref "R14") (pin "1") (pinfunction "1_1") (pintype "passive"))
    )
    (net (code "121") (name "/USB_DVL_M") (class "Default")
      (node (ref "IC2") (pin "16") (pinfunction "USBDM_16") (pintype "bidirectional"))
      (node (ref "KK396_1") (pin "P$10") (pinfunction "P$10_P$10") (pintype "bidirectional"))
    )
    (net (code "122") (name "/USB_DVL_P") (class "Default")
      (node (ref "IC2") (pin "15") (pinfunction "USBDP_15") (pintype "bidirectional"))
      (node (ref "KK396_1") (pin "P$11") (pinfunction "P$11_P$11") (pintype "bidirectional"))
    )
    (net (code "123") (name "/USB_UP_M") (class "Default")
      (node (ref "G4") (pin "C") (pinfunction "C_C") (pintype "bidirectional"))
      (node (ref "KK396_1") (pin "P$2") (pinfunction "P$2_P$2") (pintype "bidirectional"))
      (node (ref "R2") (pin "1") (pinfunction "1_1") (pintype "passive"))
    )
    (net (code "124") (name "/USB_UP_P") (class "Default")
      (node (ref "G4") (pin "D") (pinfunction "D_D") (pintype "bidirectional"))
      (node (ref "KK396_1") (pin "P$1") (pinfunction "P$1_P$1") (pintype "bidirectional"))
      (node (ref "R1") (pin "1") (pinfunction "1_1") (pintype "passive"))
    )
    (net (code "125") (name "/USB_VCC") (class "Default")
      (node (ref "C11") (pin "1") (pinfunction "1_1") (pintype "passive"))
      (node (ref "G5") (pin "3") (pinfunction "OUT_3") (pintype "bidirectional"))
      (node (ref "USB_CONTROLLER") (pin "25") (pinfunction "VCC_25") (pintype "power_in"))
      (node (ref "USB_CONTROLLER") (pin "3") (pinfunction "VCC_3") (pintype "power_in"))
    )
    (net (code "126") (name "/V_USB1") (class "Default")
      (node (ref "G8") (pin "-") (pinfunction "-_-") (pintype "bidirectional"))
      (node (ref "USB_CURRENT") (pin "OUT1") (pinfunction "OUT1_OUT1") (pintype "bidirectional"))
    )
    (net (code "127") (name "/V_USB2") (class "Default")
      (node (ref "G9") (pin "+") (pinfunction "+_+") (pintype "bidirectional"))
      (node (ref "USB_CURRENT") (pin "OUT2") (pinfunction "OUT2_OUT2") (pintype "bidirectional"))
    )
    (net (code "128") (name "/V_USB3") (class "Default")
      (node (ref "G7") (pin "+") (pinfunction "+_+") (pintype "bidirectional"))
      (node (ref "POWER_BOARD") (pin "20") (pinfunction "P$20_20") (pintype "bidirectional"))
      (node (ref "SENSOR_BOARD") (pin "20") (pinfunction "P$20_20") (pintype "bidirectional"))
      (node (ref "SONAR_BOARD") (pin "20") (pinfunction "P$20_20") (pintype "bidirectional"))
      (node (ref "USB_CURRENT") (pin "OUT3") (pinfunction "OUT3_OUT3") (pintype "bidirectional"))
    )
    (net (code "129") (name "/V_USB4") (class "Default")
      (node (ref "ARM_BOARD") (pin "20") (pinfunction "P$20_20") (pintype "bidirectional"))
      (node (ref "G6") (pin "+") (pinfunction "+_+") (pintype "bidirectional"))
      (node (ref "USB_CURRENT") (pin "OUT4") (pinfunction "OUT4_OUT4") (pintype "bidirectional"))
    )
    (net (code "130") (name "/XTAL1") (class "Default")
      (node (ref "USB_CONTROLLER") (pin "30") (pinfunction "XTAL1_30") (pintype "input"))
    )
    (net (code "131") (name "/XTAL2") (class "Default")
      (node (ref "USB_CONTROLLER") (pin "29") (pinfunction "XTAL2_29") (pintype "output"))
    )
    (net (code "132") (name "/~{OVRCUR1}") (class "Default")
      (node (ref "USB_CONTROLLER") (pin "10") (pinfunction "~{OVRCUR1}_10") (pintype "input"))
      (node (ref "USB_CURRENT") (pin "!OC1!") (pinfunction "~{OC1}_!OC1!") (pintype "bidirectional"))
    )
    (net (code "133") (name "/~{OVRCUR2}") (class "Default")
      (node (ref "USB_CONTROLLER") (pin "14") (pinfunction "~{OVRCUR2}_14") (pintype "input"))
      (node (ref "USB_CURRENT") (pin "!OC2!") (pinfunction "~{OC2}_!OC2!") (pintype "bidirectional"))
    )
    (net (code "134") (name "/~{OVRCUR3}") (class "Default")
      (node (ref "USB_CONTROLLER") (pin "18") (pinfunction "~{OVRCUR3}_18") (pintype "input"))
      (node (ref "USB_CURRENT") (pin "!OC3!") (pinfunction "~{OC3}_!OC3!") (pintype "bidirectional"))
    )
    (net (code "135") (name "/~{OVRCUR4}") (class "Default")
      (node (ref "USB_CONTROLLER") (pin "22") (pinfunction "~{OVRCUR4}_22") (pintype "input"))
      (node (ref "USB_CURRENT") (pin "!OC4!") (pinfunction "~{OC4}_!OC4!") (pintype "bidirectional"))
    )
    (net (code "136") (name "/~{PWRON1}") (class "Default")
      (node (ref "USB_CONTROLLER") (pin "9") (pinfunction "~{PWRON1}_9") (pintype "output"))
      (node (ref "USB_CURRENT") (pin "!EN1!") (pinfunction "~{EN1}_!EN1!") (pintype "bidirectional"))
    )
    (net (code "137") (name "/~{PWRON2}") (class "Default")
      (node (ref "USB_CONTROLLER") (pin "13") (pinfunction "~{PWRON2}_13") (pintype "output"))
      (node (ref "USB_CURRENT") (pin "!EN2!") (pinfunction "~{EN2}_!EN2!") (pintype "bidirectional"))
    )
    (net (code "138") (name "/~{PWRON3}") (class "Default")
      (node (ref "USB_CONTROLLER") (pin "17") (pinfunction "~{PWRON3}_17") (pintype "output"))
      (node (ref "USB_CURRENT") (pin "!EN3!") (pinfunction "~{EN3}_!EN3!") (pintype "bidirectional"))
    )
    (net (code "139") (name "/~{PWRON4}") (class "Default")
      (node (ref "USB_CONTROLLER") (pin "21") (pinfunction "~{PWRON4}_21") (pintype "output"))
      (node (ref "USB_CURRENT") (pin "!EN4!") (pinfunction "~{EN4}_!EN4!") (pintype "bidirectional"))
    )
    (net (code "140") (name "Net-(C25-Pad1)") (class "Default")
      (node (ref "C25") (pin "1") (pinfunction "1_1") (pintype "passive"))
      (node (ref "G1") (pin "FILTER") (pinfunction "FILTER_FILTER") (pintype "bidirectional"))
    )
    (net (code "141") (name "Net-(C26-Pad1)") (class "Default")
      (node (ref "C26") (pin "1") (pinfunction "1_1") (pintype "passive"))
      (node (ref "G1") (pin "VCC") (pinfunction "VCC_VCC") (pintype "bidirectional"))
    )
    (net (code "142") (name "Net-(C27-Pad1)") (class "Default")
      (node (ref "C27") (pin "1") (pinfunction "1_1") (pintype "passive"))
      (node (ref "G10") (pin "FILTER") (pinfunction "FILTER_FILTER") (pintype "bidirectional"))
    )
    (net (code "143") (name "Net-(C28-Pad1)") (class "Default")
      (node (ref "C28") (pin "1") (pinfunction "1_1") (pintype "passive"))
      (node (ref "G10") (pin "VCC") (pinfunction "VCC_VCC") (pintype "bidirectional"))
    )
    (net (code "144") (name "Net-(C29-Pad1)") (class "Default")
      (node (ref "C29") (pin "1") (pinfunction "1_1") (pintype "passive"))
      (node (ref "G11") (pin "FILTER") (pinfunction "FILTER_FILTER") (pintype "bidirectional"))
    )
    (net (code "145") (name "Net-(C30-Pad1)") (class "Default")
      (node (ref "C30") (pin "1") (pinfunction "1_1") (pintype "passive"))
      (node (ref "G11") (pin "VCC") (pinfunction "VCC_VCC") (pintype "bidirectional"))
    )
    (net (code "146") (name "Net-(C31-Pad1)") (class "Default")
      (node (ref "C31") (pin "1") (pinfunction "1_1") (pintype "passive"))
      (node (ref "G12") (pin "FILTER") (pinfunction "FILTER_FILTER") (pintype "bidirectional"))
    )
    (net (code "147") (name "Net-(C32-Pad1)") (class "Default")
      (node (ref "C32") (pin "1") (pinfunction "1_1") (pintype "passive"))
      (node (ref "G12") (pin "VCC") (pinfunction "VCC_VCC") (pintype "bidirectional"))
    )
    (net (code "148") (name "Net-(C33-Pad1)") (class "Default")
      (node (ref "C33") (pin "1") (pinfunction "1_1") (pintype "passive"))
      (node (ref "G13") (pin "FILTER") (pinfunction "FILTER_FILTER") (pintype "bidirectional"))
    )
    (net (code "149") (name "Net-(C34-Pad1)") (class "Default")
      (node (ref "C34") (pin "1") (pinfunction "1_1") (pintype "passive"))
      (node (ref "G13") (pin "VCC") (pinfunction "VCC_VCC") (pintype "bidirectional"))
    )
    (net (code "150") (name "Net-(C35-Pad1)") (class "Default")
      (node (ref "C35") (pin "1") (pinfunction "1_1") (pintype "passive"))
      (node (ref "G14") (pin "FILTER") (pinfunction "FILTER_FILTER") (pintype "bidirectional"))
    )
    (net (code "151") (name "Net-(C36-Pad1)") (class "Default")
      (node (ref "C36") (pin "1") (pinfunction "1_1") (pintype "passive"))
      (node (ref "G14") (pin "VCC") (pinfunction "VCC_VCC") (pintype "bidirectional"))
    )
    (net (code "152") (name "Net-(C37-Pad1)") (class "Default")
      (node (ref "C37") (pin "1") (pinfunction "1_1") (pintype "passive"))
      (node (ref "G15") (pin "FILTER") (pinfunction "FILTER_FILTER") (pintype "bidirectional"))
    )
    (net (code "153") (name "Net-(C38-Pad1)") (class "Default")
      (node (ref "C38") (pin "1") (pinfunction "1_1") (pintype "passive"))
      (node (ref "G15") (pin "VCC") (pinfunction "VCC_VCC") (pintype "bidirectional"))
    )
    (net (code "154") (name "Net-(C39-Pad1)") (class "Default")
      (node (ref "C39") (pin "1") (pinfunction "1_1") (pintype "passive"))
      (node (ref "G16") (pin "FILTER") (pinfunction "FILTER_FILTER") (pintype "bidirectional"))
    )
    (net (code "155") (name "Net-(C40-Pad1)") (class "Default")
      (node (ref "C40") (pin "1") (pinfunction "1_1") (pintype "passive"))
      (node (ref "G16") (pin "VCC") (pinfunction "VCC_VCC") (pintype "bidirectional"))
    )
    (net (code "156") (name "Net-(IC2-3V3OUT)") (class "Default")
      (node (ref "C44") (pin "1") (pinfunction "1_1") (pintype "passive"))
      (node (ref "IC2") (pin "17") (pinfunction "3V3OUT_17") (pintype "output"))
    )
    (net (code "157") (name "Net-(R24-Pad2)") (class "Default")
      (node (ref "R24") (pin "2") (pinfunction "2_2") (pintype "passive"))
      (node (ref "R25") (pin "2") (pinfunction "2_2") (pintype "passive"))
      (node (ref "THRUSTER_PWR_SWTICH") (pin "P$1") (pinfunction "P$1_P$1") (pintype "bidirectional"))
    )
    (net (code "158") (name "Net-(U$9A-C1+)") (class "Default")
      (node (ref "C48") (pin "1") (pinfunction "1_1") (pintype "passive"))
      (node (ref "U$9") (pin "12") (pinfunction "C1+_12") (pintype "passive"))
    )
    (net (code "159") (name "Net-(U$9A-C1-)") (class "Default")
      (node (ref "C48") (pin "2") (pinfunction "2_2") (pintype "passive"))
      (node (ref "U$9") (pin "14") (pinfunction "C1-_14") (pintype "passive"))
    )
    (net (code "160") (name "Net-(U$9A-C2+)") (class "Default")
      (node (ref "C49") (pin "1") (pinfunction "1_1") (pintype "passive"))
      (node (ref "U$9") (pin "15") (pinfunction "C2+_15") (pintype "passive"))
    )
    (net (code "161") (name "Net-(U$9A-C2-)") (class "Default")
      (node (ref "C49") (pin "2") (pinfunction "2_2") (pintype "passive"))
      (node (ref "U$9") (pin "16") (pinfunction "C2-_16") (pintype "passive"))
    )
    (net (code "162") (name "Net-(U$9A-V+)") (class "Default")
      (node (ref "C46") (pin "1") (pinfunction "1_1") (pintype "passive"))
      (node (ref "U$9") (pin "13") (pinfunction "V+_13") (pintype "passive"))
    )
    (net (code "163") (name "Net-(U$9A-V-)") (class "Default")
      (node (ref "C47") (pin "2") (pinfunction "2_2") (pintype "passive"))
      (node (ref "U$9") (pin "17") (pinfunction "V-_17") (pintype "passive"))
    )
    (net (code "164") (name "Net-(USB_CONTROLLER-DM0)") (class "Default")
      (node (ref "C1") (pin "1") (pinfunction "1_1") (pintype "passive"))
      (node (ref "R2") (pin "2") (pinfunction "2_2") (pintype "passive"))
      (node (ref "USB_CONTROLLER") (pin "2") (pinfunction "DM0_2") (pintype "bidirectional"))
    )
    (net (code "165") (name "Net-(USB_CONTROLLER-DM1)") (class "Default")
      (node (ref "C4") (pin "1") (pinfunction "1_1") (pintype "passive"))
      (node (ref "R4") (pin "2") (pinfunction "2_2") (pintype "passive"))
      (node (ref "USB_CONTROLLER") (pin "11") (pinfunction "DM1_11") (pintype "bidirectional"))
    )
    (net (code "166") (name "Net-(USB_CONTROLLER-DM2)") (class "Default")
      (node (ref "C6") (pin "1") (pinfunction "1_1") (pintype "passive"))
      (node (ref "R6") (pin "2") (pinfunction "2_2") (pintype "passive"))
      (node (ref "USB_CONTROLLER") (pin "15") (pinfunction "DM2_15") (pintype "bidirectional"))
    )
    (net (code "167") (name "Net-(USB_CONTROLLER-DM3)") (class "Default")
      (node (ref "C8") (pin "1") (pinfunction "1_1") (pintype "passive"))
      (node (ref "R18") (pin "1") (pinfunction "1_1") (pintype "passive"))
      (node (ref "R19") (pin "2") (pinfunction "2_2") (pintype "passive"))
      (node (ref "USB_CONTROLLER") (pin "19") (pinfunction "DM3_19") (pintype "bidirectional"))
    )
    (net (code "168") (name "Net-(USB_CONTROLLER-DM4)") (class "Default")
      (node (ref "C9") (pin "1") (pinfunction "1_1") (pintype "passive"))
      (node (ref "R13") (pin "2") (pinfunction "2_2") (pintype "passive"))
      (node (ref "USB_CONTROLLER") (pin "23") (pinfunction "DM4_23") (pintype "bidirectional"))
    )
    (net (code "169") (name "Net-(USB_CONTROLLER-DP0)") (class "Default")
      (node (ref "C2") (pin "1") (pinfunction "1_1") (pintype "passive"))
      (node (ref "R1") (pin "2") (pinfunction "2_2") (pintype "passive"))
      (node (ref "R3") (pin "1") (pinfunction "1_1") (pintype "passive"))
      (node (ref "USB_CONTROLLER") (pin "1") (pinfunction "DP0_1") (pintype "bidirectional"))
    )
    (net (code "170") (name "Net-(USB_CONTROLLER-DP1)") (class "Default")
      (node (ref "C3") (pin "1") (pinfunction "1_1") (pintype "passive"))
      (node (ref "R5") (pin "2") (pinfunction "2_2") (pintype "passive"))
      (node (ref "USB_CONTROLLER") (pin "12") (pinfunction "DP1_12") (pintype "bidirectional"))
    )
    (net (code "171") (name "Net-(USB_CONTROLLER-DP2)") (class "Default")
      (node (ref "C5") (pin "1") (pinfunction "1_1") (pintype "passive"))
      (node (ref "R7") (pin "2") (pinfunction "2_2") (pintype "passive"))
      (node (ref "USB_CONTROLLER") (pin "16") (pinfunction "DP2_16") (pintype "bidirectional"))
    )
    (net (code "172") (name "Net-(USB_CONTROLLER-DP3)") (class "Default")
      (node (ref "C7") (pin "1") (pinfunction "1_1") (pintype "passive"))
      (node (ref "R16") (pin "1") (pinfunction "1_1") (pintype "passive"))
      (node (ref "R17") (pin "1") (pinfunction "1_1") (pintype "passive"))
      (node (ref "USB_CONTROLLER") (pin "20") (pinfunction "DP3_20") (pintype "bidirectional"))
    )
    (net (code "173") (name "Net-(USB_CONTROLLER-DP4)") (class "Default")
      (node (ref "C10") (pin "1") (pinfunction "1_1") (pintype "passive"))
      (node (ref "R12") (pin "1") (pinfunction "1_1") (pintype "passive"))
      (node (ref "USB_CONTROLLER") (pin "24") (pinfunction "DP4_24") (pintype "bidirectional"))
    )
    (net (code "174") (name "unconnected-(G4-PadA)") (class "Default")
      (node (ref "G4") (pin "A") (pinfunction "A_A") (pintype "bidirectional"))
    )
    (net (code "175") (name "unconnected-(G4-PadB)") (class "Default")
      (node (ref "G4") (pin "B") (pinfunction "B_B") (pintype "bidirectional"))
    )
    (net (code "176") (name "unconnected-(HDAC1-PadP$17)") (class "Default")
      (node (ref "HDAC1") (pin "P$17") (pinfunction "P$17_P$17") (pintype "bidirectional"))
    )
    (net (code "177") (name "unconnected-(HDAC1-PadP$18)") (class "Default")
      (node (ref "HDAC1") (pin "P$18") (pinfunction "P$18_P$18") (pintype "bidirectional"))
    )
    (net (code "178") (name "unconnected-(HDAC1-PadP$19)") (class "Default")
      (node (ref "HDAC1") (pin "P$19") (pinfunction "P$19_P$19") (pintype "bidirectional"))
    )
    (net (code "179") (name "unconnected-(HDAC1-PadP$20)") (class "Default")
      (node (ref "HDAC1") (pin "P$20") (pinfunction "P$20_P$20") (pintype "bidirectional"))
    )
    (net (code "180") (name "unconnected-(IC2-CBUS0-Pad23)") (class "Default")
      (node (ref "IC2") (pin "23") (pinfunction "CBUS0_23") (pintype "bidirectional"))
    )
    (net (code "181") (name "unconnected-(IC2-CBUS1-Pad22)") (class "Default")
      (node (ref "IC2") (pin "22") (pinfunction "CBUS1_22") (pintype "bidirectional"))
    )
    (net (code "182") (name "unconnected-(IC2-CBUS2-Pad13)") (class "Default")
      (node (ref "IC2") (pin "13") (pinfunction "CBUS2_13") (pintype "bidirectional"))
    )
    (net (code "183") (name "unconnected-(IC2-CBUS3-Pad14)") (class "Default")
      (node (ref "IC2") (pin "14") (pinfunction "CBUS3_14") (pintype "bidirectional"))
    )
    (net (code "184") (name "unconnected-(IC2-OSCI-Pad27)") (class "Default")
      (node (ref "IC2") (pin "27") (pinfunction "OSCI_27") (pintype "input"))
    )
    (net (code "185") (name "unconnected-(IC2-OSCO-Pad28)") (class "Default")
      (node (ref "IC2") (pin "28") (pinfunction "OSCO_28") (pintype "output"))
    )
    (net (code "186") (name "unconnected-(IC2-~{DCD}-Pad10)") (class "Default")
      (node (ref "IC2") (pin "10") (pinfunction "~{DCD}_10") (pintype "input"))
    )
    (net (code "187") (name "unconnected-(IC2-~{DTR}-Pad2)") (class "Default")
      (node (ref "IC2") (pin "2") (pinfunction "~{DTR}_2") (pintype "output"))
    )
    (net (code "188") (name "unconnected-(IC2-~{RI}-Pad6)") (class "Default")
      (node (ref "IC2") (pin "6") (pinfunction "~{RI}_6") (pintype "input"))
    )
    (net (code "189") (name "unconnected-(IC2-~{RTS}-Pad3)") (class "Default")
      (node (ref "IC2") (pin "3") (pinfunction "~{RTS}_3") (pintype "output"))
    )
    (net (code "190") (name "unconnected-(PICOCLASP1-PadP$18)") (class "Default")
      (node (ref "PICOCLASP1") (pin "P$18") (pinfunction "P$18_P$18") (pintype "bidirectional"))
    )
    (net (code "191") (name "unconnected-(PICOCLASP1-PadP$19)") (class "Default")
      (node (ref "PICOCLASP1") (pin "P$19") (pinfunction "P$19_P$19") (pintype "bidirectional"))
    )
    (net (code "192") (name "unconnected-(PICOCLASP1-PadP$20)") (class "Default")
      (node (ref "PICOCLASP1") (pin "P$20") (pinfunction "P$20_P$20") (pintype "bidirectional"))
    )
    (net (code "193") (name "unconnected-(PICOCLASP1-PadP$39)") (class "Default")
      (node (ref "PICOCLASP1") (pin "P$39") (pinfunction "P$39_P$39") (pintype "bidirectional"))
    )
    (net (code "194") (name "unconnected-(PICOCLASP1-PadP$40)") (class "Default")
      (node (ref "PICOCLASP1") (pin "P$40") (pinfunction "P$40_P$40") (pintype "bidirectional"))
    )
    (net (code "195") (name "unconnected-(U$9A-R4IN-Pad23)") (class "Default")
      (node (ref "U$9") (pin "23") (pinfunction "R4IN_23") (pintype "input"))
    )
    (net (code "196") (name "unconnected-(U$9A-R5IN-Pad18)") (class "Default")
      (node (ref "U$9") (pin "18") (pinfunction "R5IN_18") (pintype "input"))
    )
    (net (code "197") (name "unconnected-(U$9A-T4IN-Pad21)") (class "Default")
      (node (ref "U$9") (pin "21") (pinfunction "T4IN_21") (pintype "input"))
    )
    (net (code "198") (name "unconnected-(U$9A-T4OUT-Pad28)") (class "Default")
      (node (ref "U$9") (pin "28") (pinfunction "T4OUT_28") (pintype "output"))
    )
    (net (code "199") (name "unconnected-(USB_CONTROLLER-EECLK-Pad5)") (class "Default")
      (node (ref "USB_CONTROLLER") (pin "5") (pinfunction "EECLK_5") (pintype "output"))
    )
  )
)
